# BMSBoard.net
KiCad netlist of a schematic drawn in EAGLE
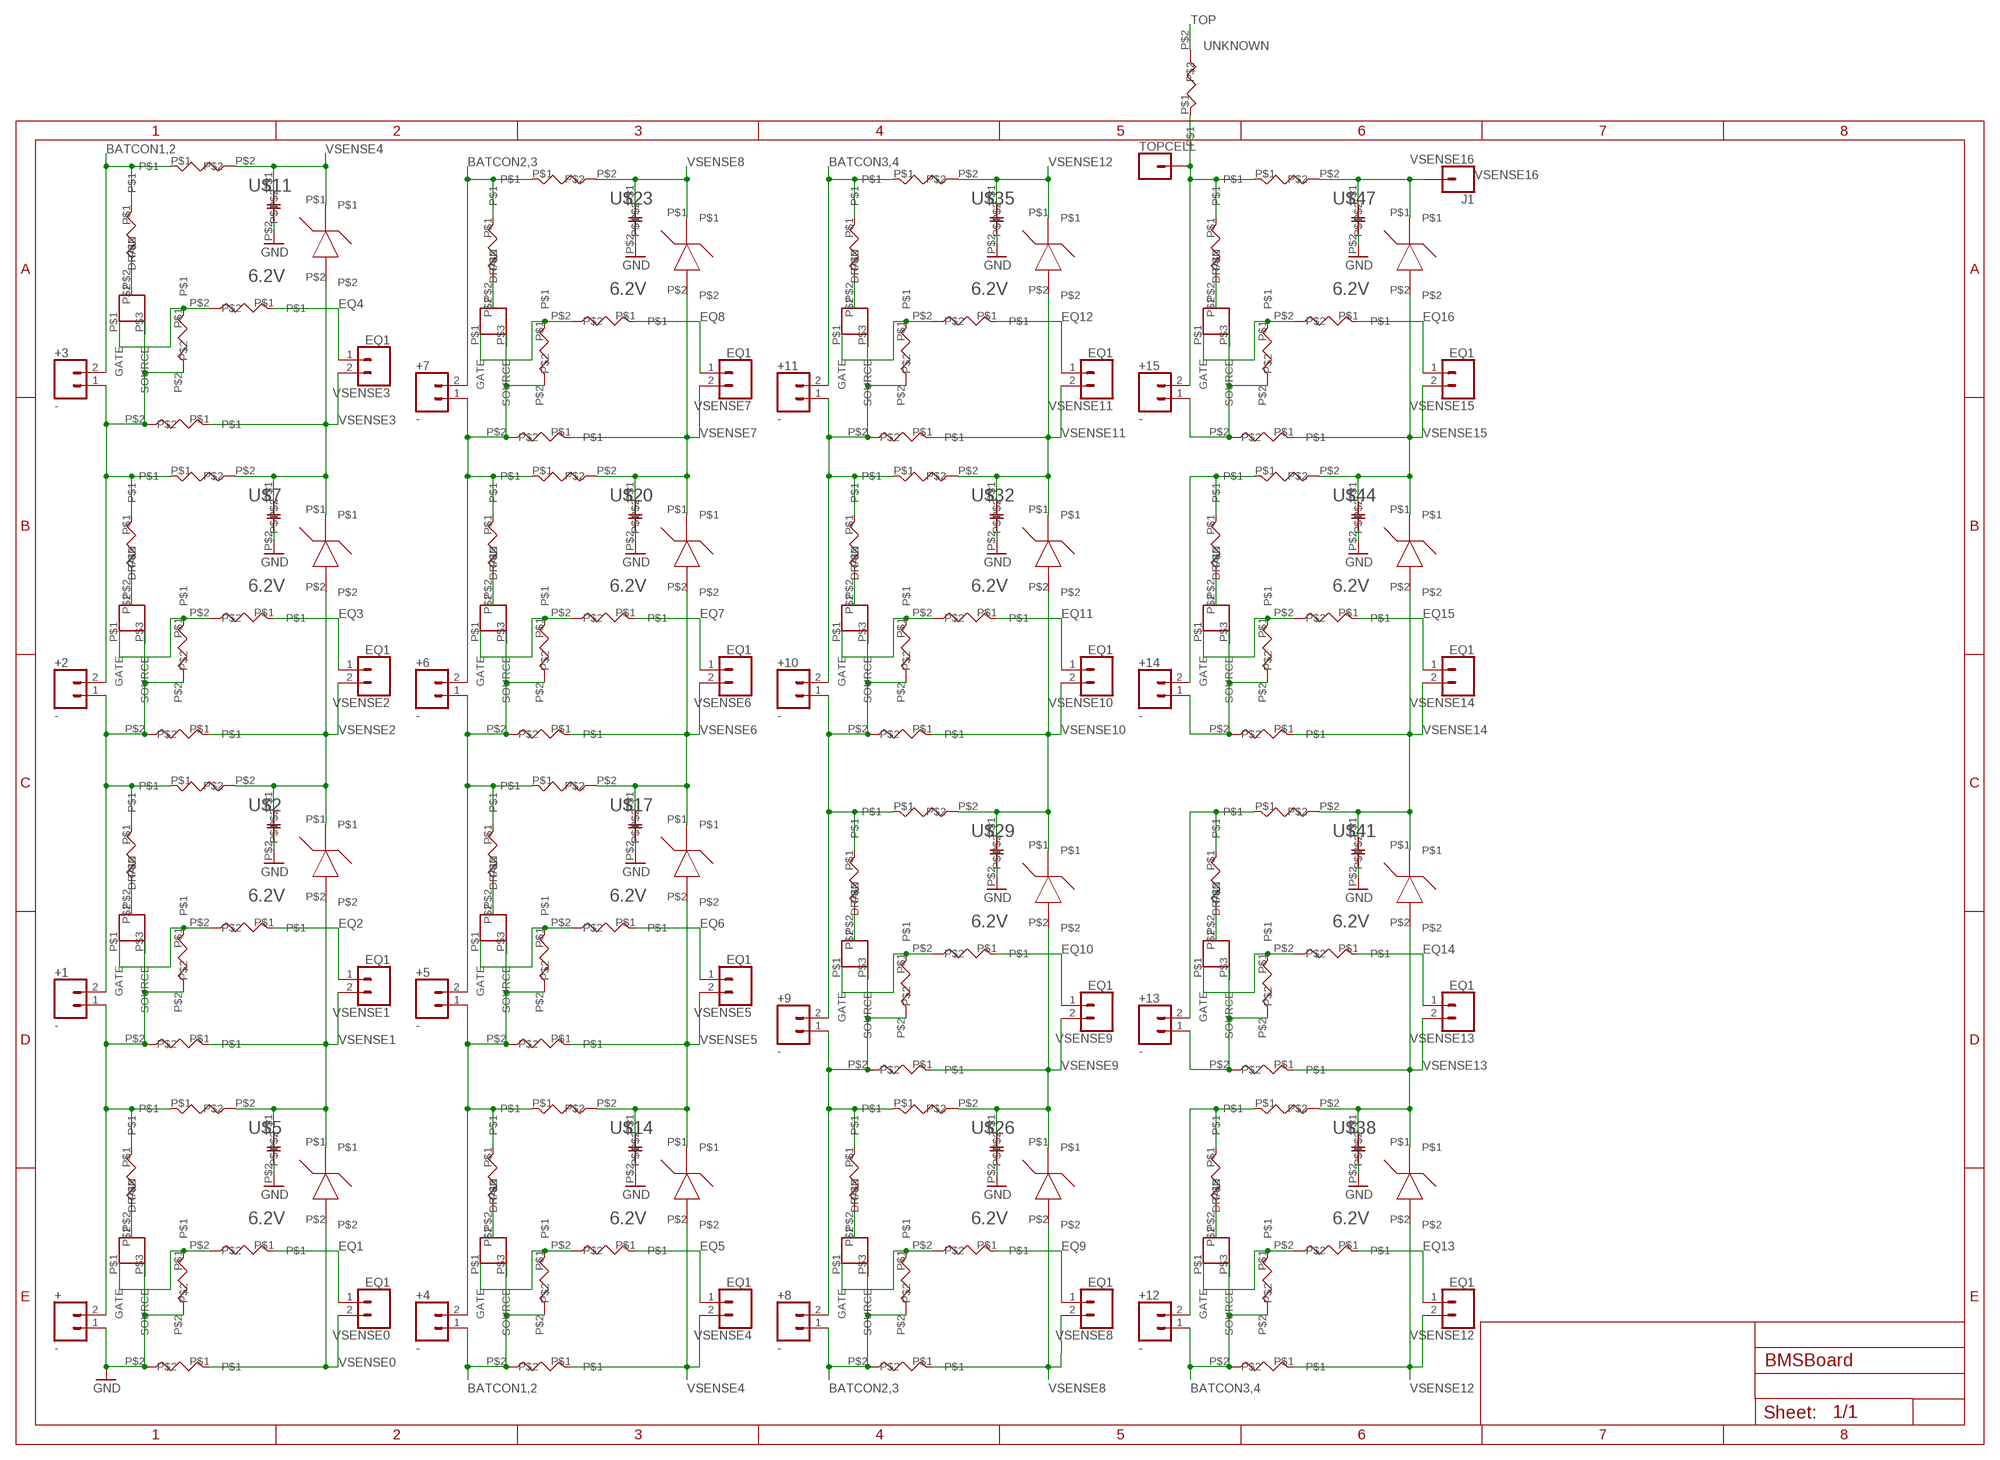
[diagram p0: schematic, sheet 1, part 1 of 2]
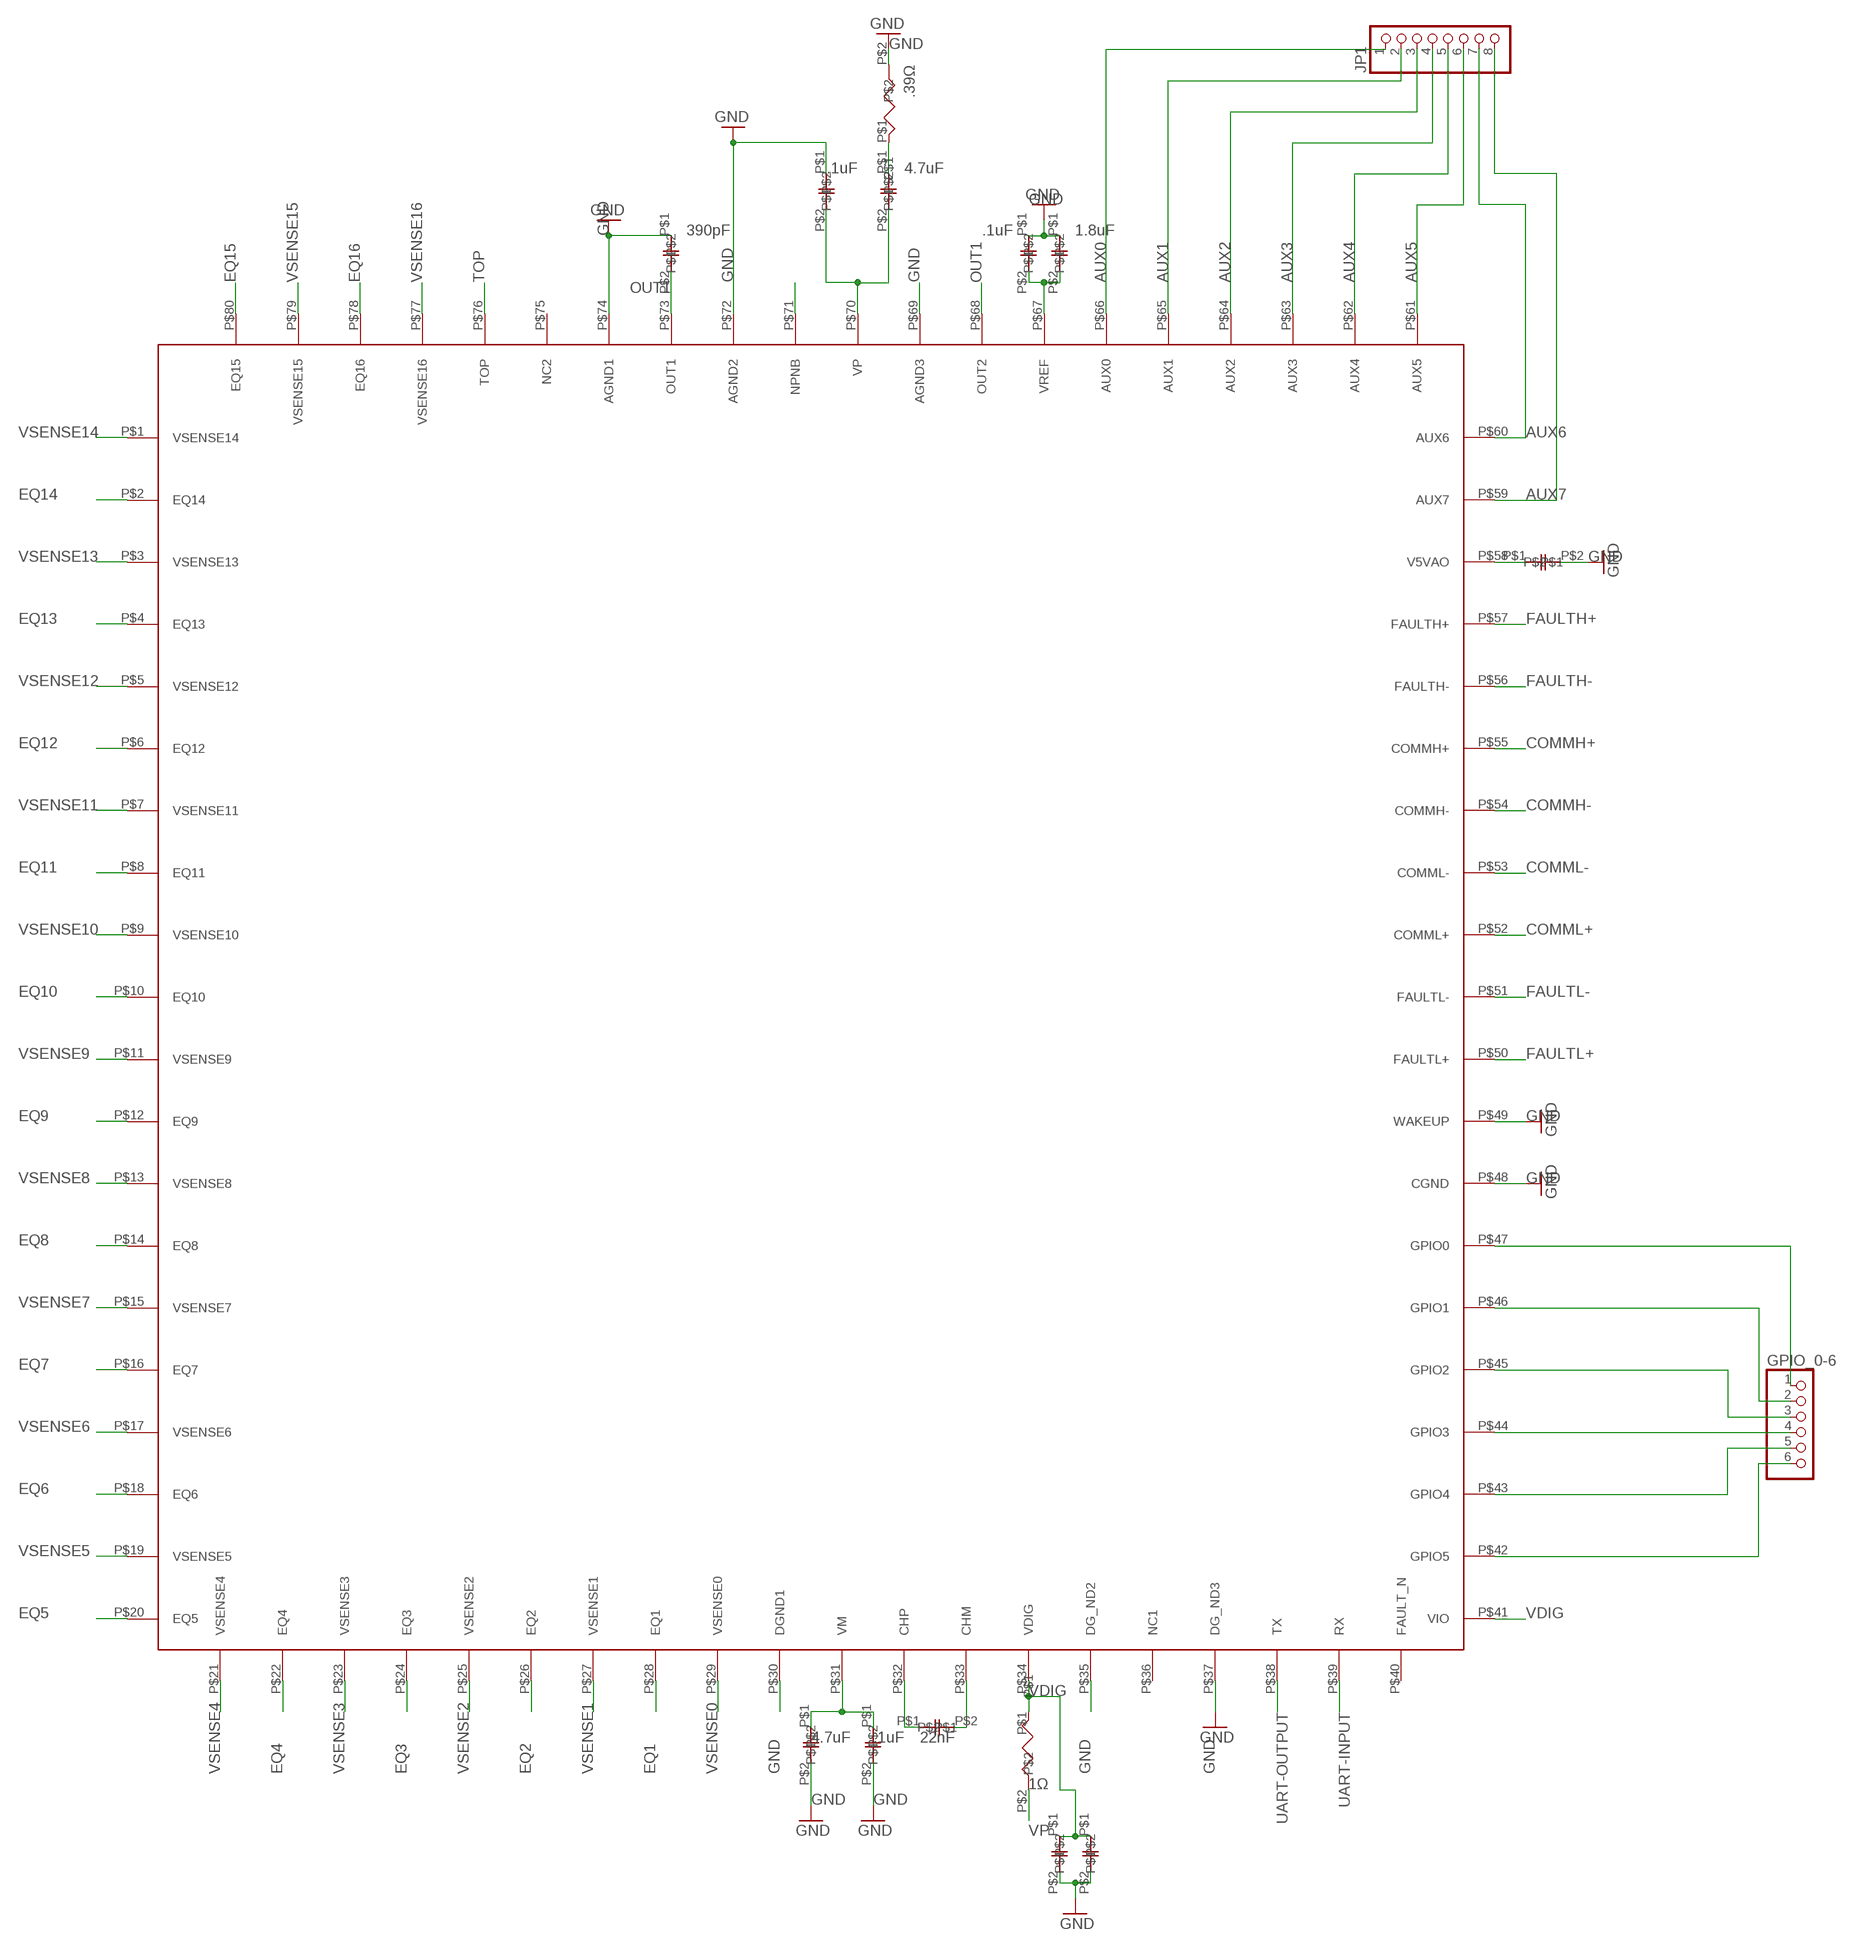
[diagram p1: schematic, sheet 1, part 2 of 2]

(export (version "E")
  (design (tool "Eeschema 10.0.6"))
  (components
    (comp (ref "+")
      (value "-")
      (footprint "eagle-import:1X02")
      (libsource (lib "eagle-import") (part "CONN_02"))
    )
    (comp (ref "+1")
      (value "-")
      (footprint "eagle-import:1X02")
      (libsource (lib "eagle-import") (part "CONN_02"))
    )
    (comp (ref "+2")
      (value "-")
      (footprint "eagle-import:1X02")
      (libsource (lib "eagle-import") (part "CONN_02"))
    )
    (comp (ref "+3")
      (value "-")
      (footprint "eagle-import:1X02")
      (libsource (lib "eagle-import") (part "CONN_02"))
    )
    (comp (ref "+4")
      (value "-")
      (footprint "eagle-import:1X02")
      (libsource (lib "eagle-import") (part "CONN_02"))
    )
    (comp (ref "+5")
      (value "-")
      (footprint "eagle-import:1X02")
      (libsource (lib "eagle-import") (part "CONN_02"))
    )
    (comp (ref "+6")
      (value "-")
      (footprint "eagle-import:1X02")
      (libsource (lib "eagle-import") (part "CONN_02"))
    )
    (comp (ref "+7")
      (value "-")
      (footprint "eagle-import:1X02")
      (libsource (lib "eagle-import") (part "CONN_02"))
    )
    (comp (ref "+8")
      (value "-")
      (footprint "eagle-import:1X02")
      (libsource (lib "eagle-import") (part "CONN_02"))
    )
    (comp (ref "+9")
      (value "-")
      (footprint "eagle-import:1X02")
      (libsource (lib "eagle-import") (part "CONN_02"))
    )
    (comp (ref "+10")
      (value "-")
      (footprint "eagle-import:1X02")
      (libsource (lib "eagle-import") (part "CONN_02"))
    )
    (comp (ref "+11")
      (value "-")
      (footprint "eagle-import:1X02")
      (libsource (lib "eagle-import") (part "CONN_02"))
    )
    (comp (ref "+12")
      (value "-")
      (footprint "eagle-import:1X02")
      (libsource (lib "eagle-import") (part "CONN_02"))
    )
    (comp (ref "+13")
      (value "-")
      (footprint "eagle-import:1X02")
      (libsource (lib "eagle-import") (part "CONN_02"))
    )
    (comp (ref "+14")
      (value "-")
      (footprint "eagle-import:1X02")
      (libsource (lib "eagle-import") (part "CONN_02"))
    )
    (comp (ref "+15")
      (value "-")
      (footprint "eagle-import:1X02")
      (libsource (lib "eagle-import") (part "CONN_02"))
    )
    (comp (ref "1UF")
      (value "1uF")
      (footprint "eagle-import:CL21B105KBFNNNG")
      (libsource (lib "eagle-import") (part "CL21B105KBFNNNG"))
    )
    (comp (ref "1UF1")
      (value "1uF")
      (footprint "eagle-import:CL21B105KBFNNNG")
      (libsource (lib "eagle-import") (part "CL21B105KBFNNNG"))
    )
    (comp (ref "1UF2")
      (value "1uF")
      (footprint "eagle-import:CL21B105KBFNNNG")
      (libsource (lib "eagle-import") (part "CL21B105KBFNNNG"))
    )
    (comp (ref "1UF3")
      (value "1uF")
      (footprint "eagle-import:CL21B105KBFNNNG")
      (libsource (lib "eagle-import") (part "CL21B105KBFNNNG"))
    )
    (comp (ref "1UF4")
      (value "1uF")
      (footprint "eagle-import:CL21B105KBFNNNG")
      (libsource (lib "eagle-import") (part "CL21B105KBFNNNG"))
    )
    (comp (ref "1UF5")
      (value "1uF")
      (footprint "eagle-import:CL21B105KBFNNNG")
      (libsource (lib "eagle-import") (part "CL21B105KBFNNNG"))
    )
    (comp (ref "1UF6")
      (value "1uF")
      (footprint "eagle-import:CL21B105KBFNNNG")
      (libsource (lib "eagle-import") (part "CL21B105KBFNNNG"))
    )
    (comp (ref "1UF7")
      (value "1uF")
      (footprint "eagle-import:CL21B105KBFNNNG")
      (libsource (lib "eagle-import") (part "CL21B105KBFNNNG"))
    )
    (comp (ref "1UF8")
      (value "1uF")
      (footprint "eagle-import:CL21B105KBFNNNG")
      (libsource (lib "eagle-import") (part "CL21B105KBFNNNG"))
    )
    (comp (ref "1UF9")
      (value "1uF")
      (footprint "eagle-import:CL21B105KBFNNNG")
      (libsource (lib "eagle-import") (part "CL21B105KBFNNNG"))
    )
    (comp (ref "1UF10")
      (value "1uF")
      (footprint "eagle-import:CL21B105KBFNNNG")
      (libsource (lib "eagle-import") (part "CL21B105KBFNNNG"))
    )
    (comp (ref "1UF11")
      (value "1uF")
      (footprint "eagle-import:CL21B105KBFNNNG")
      (libsource (lib "eagle-import") (part "CL21B105KBFNNNG"))
    )
    (comp (ref "1UF12")
      (value "1uF")
      (footprint "eagle-import:CL21B105KBFNNNG")
      (libsource (lib "eagle-import") (part "CL21B105KBFNNNG"))
    )
    (comp (ref "1UF13")
      (value "1uF")
      (footprint "eagle-import:CL21B105KBFNNNG")
      (libsource (lib "eagle-import") (part "CL21B105KBFNNNG"))
    )
    (comp (ref "1UF14")
      (value "1uF")
      (footprint "eagle-import:CL21B105KBFNNNG")
      (libsource (lib "eagle-import") (part "CL21B105KBFNNNG"))
    )
    (comp (ref "1UF15")
      (value "1uF")
      (footprint "eagle-import:CL21B105KBFNNNG")
      (libsource (lib "eagle-import") (part "CL21B105KBFNNNG"))
    )
    (comp (ref "2KΩ")
      (value "2kΩ")
      (footprint "eagle-import:PWR3014W1000JE")
      (libsource (lib "eagle-import") (part "PWR3014W1000JE"))
    )
    (comp (ref "2KΩ1")
      (value "2kΩ")
      (footprint "eagle-import:PWR3014W1000JE")
      (libsource (lib "eagle-import") (part "PWR3014W1000JE"))
    )
    (comp (ref "2KΩ2")
      (value "2kΩ")
      (footprint "eagle-import:PWR3014W1000JE")
      (libsource (lib "eagle-import") (part "PWR3014W1000JE"))
    )
    (comp (ref "2KΩ3")
      (value "2kΩ")
      (footprint "eagle-import:PWR3014W1000JE")
      (libsource (lib "eagle-import") (part "PWR3014W1000JE"))
    )
    (comp (ref "2KΩ4")
      (value "2kΩ")
      (footprint "eagle-import:PWR3014W1000JE")
      (libsource (lib "eagle-import") (part "PWR3014W1000JE"))
    )
    (comp (ref "2KΩ5")
      (value "2kΩ")
      (footprint "eagle-import:PWR3014W1000JE")
      (libsource (lib "eagle-import") (part "PWR3014W1000JE"))
    )
    (comp (ref "2KΩ6")
      (value "2kΩ")
      (footprint "eagle-import:PWR3014W1000JE")
      (libsource (lib "eagle-import") (part "PWR3014W1000JE"))
    )
    (comp (ref "2KΩ7")
      (value "2kΩ")
      (footprint "eagle-import:PWR3014W1000JE")
      (libsource (lib "eagle-import") (part "PWR3014W1000JE"))
    )
    (comp (ref "2KΩ8")
      (value "2kΩ")
      (footprint "eagle-import:PWR3014W1000JE")
      (libsource (lib "eagle-import") (part "PWR3014W1000JE"))
    )
    (comp (ref "2KΩ9")
      (value "2kΩ")
      (footprint "eagle-import:PWR3014W1000JE")
      (libsource (lib "eagle-import") (part "PWR3014W1000JE"))
    )
    (comp (ref "2KΩ10")
      (value "2kΩ")
      (footprint "eagle-import:PWR3014W1000JE")
      (libsource (lib "eagle-import") (part "PWR3014W1000JE"))
    )
    (comp (ref "2KΩ11")
      (value "2kΩ")
      (footprint "eagle-import:PWR3014W1000JE")
      (libsource (lib "eagle-import") (part "PWR3014W1000JE"))
    )
    (comp (ref "2KΩ12")
      (value "2kΩ")
      (footprint "eagle-import:PWR3014W1000JE")
      (libsource (lib "eagle-import") (part "PWR3014W1000JE"))
    )
    (comp (ref "2KΩ13")
      (value "2kΩ")
      (footprint "eagle-import:PWR3014W1000JE")
      (libsource (lib "eagle-import") (part "PWR3014W1000JE"))
    )
    (comp (ref "2KΩ14")
      (value "2kΩ")
      (footprint "eagle-import:PWR3014W1000JE")
      (libsource (lib "eagle-import") (part "PWR3014W1000JE"))
    )
    (comp (ref "2KΩ15")
      (value "2kΩ")
      (footprint "eagle-import:PWR3014W1000JE")
      (libsource (lib "eagle-import") (part "PWR3014W1000JE"))
    )
    (comp (ref "75Ω")
      (value "75Ω")
      (footprint "eagle-import:PWR3014W1000JE")
      (libsource (lib "eagle-import") (part "PWR3014W1000JE"))
    )
    (comp (ref "75Ω1")
      (value "75Ω")
      (footprint "eagle-import:PWR3014W1000JE")
      (libsource (lib "eagle-import") (part "PWR3014W1000JE"))
    )
    (comp (ref "75Ω2")
      (value "75Ω")
      (footprint "eagle-import:PWR3014W1000JE")
      (libsource (lib "eagle-import") (part "PWR3014W1000JE"))
    )
    (comp (ref "75Ω3")
      (value "75Ω")
      (footprint "eagle-import:PWR3014W1000JE")
      (libsource (lib "eagle-import") (part "PWR3014W1000JE"))
    )
    (comp (ref "75Ω4")
      (value "75Ω")
      (footprint "eagle-import:PWR3014W1000JE")
      (libsource (lib "eagle-import") (part "PWR3014W1000JE"))
    )
    (comp (ref "75Ω5")
      (value "75Ω")
      (footprint "eagle-import:PWR3014W1000JE")
      (libsource (lib "eagle-import") (part "PWR3014W1000JE"))
    )
    (comp (ref "75Ω6")
      (value "75Ω")
      (footprint "eagle-import:PWR3014W1000JE")
      (libsource (lib "eagle-import") (part "PWR3014W1000JE"))
    )
    (comp (ref "75Ω7")
      (value "75Ω")
      (footprint "eagle-import:PWR3014W1000JE")
      (libsource (lib "eagle-import") (part "PWR3014W1000JE"))
    )
    (comp (ref "75Ω8")
      (value "75Ω")
      (footprint "eagle-import:PWR3014W1000JE")
      (libsource (lib "eagle-import") (part "PWR3014W1000JE"))
    )
    (comp (ref "75Ω9")
      (value "75Ω")
      (footprint "eagle-import:PWR3014W1000JE")
      (libsource (lib "eagle-import") (part "PWR3014W1000JE"))
    )
    (comp (ref "75Ω10")
      (value "75Ω")
      (footprint "eagle-import:PWR3014W1000JE")
      (libsource (lib "eagle-import") (part "PWR3014W1000JE"))
    )
    (comp (ref "75Ω11")
      (value "75Ω")
      (footprint "eagle-import:PWR3014W1000JE")
      (libsource (lib "eagle-import") (part "PWR3014W1000JE"))
    )
    (comp (ref "75Ω12")
      (value "75Ω")
      (footprint "eagle-import:PWR3014W1000JE")
      (libsource (lib "eagle-import") (part "PWR3014W1000JE"))
    )
    (comp (ref "75Ω13")
      (value "75Ω")
      (footprint "eagle-import:PWR3014W1000JE")
      (libsource (lib "eagle-import") (part "PWR3014W1000JE"))
    )
    (comp (ref "75Ω14")
      (value "75Ω")
      (footprint "eagle-import:PWR3014W1000JE")
      (libsource (lib "eagle-import") (part "PWR3014W1000JE"))
    )
    (comp (ref "75Ω15")
      (value "75Ω")
      (footprint "eagle-import:PWR3014W1000JE")
      (libsource (lib "eagle-import") (part "PWR3014W1000JE"))
    )
    (comp (ref "100KΩ")
      (value "100kΩ")
      (footprint "eagle-import:PWR3014W1000JE")
      (libsource (lib "eagle-import") (part "PWR3014W1000JE"))
    )
    (comp (ref "100KΩ1")
      (value "100kΩ")
      (footprint "eagle-import:PWR3014W1000JE")
      (libsource (lib "eagle-import") (part "PWR3014W1000JE"))
    )
    (comp (ref "100KΩ2")
      (value "100kΩ")
      (footprint "eagle-import:PWR3014W1000JE")
      (libsource (lib "eagle-import") (part "PWR3014W1000JE"))
    )
    (comp (ref "100KΩ3")
      (value "100kΩ")
      (footprint "eagle-import:PWR3014W1000JE")
      (libsource (lib "eagle-import") (part "PWR3014W1000JE"))
    )
    (comp (ref "100KΩ4")
      (value "100kΩ")
      (footprint "eagle-import:PWR3014W1000JE")
      (libsource (lib "eagle-import") (part "PWR3014W1000JE"))
    )
    (comp (ref "100KΩ5")
      (value "100kΩ")
      (footprint "eagle-import:PWR3014W1000JE")
      (libsource (lib "eagle-import") (part "PWR3014W1000JE"))
    )
    (comp (ref "100KΩ6")
      (value "100kΩ")
      (footprint "eagle-import:PWR3014W1000JE")
      (libsource (lib "eagle-import") (part "PWR3014W1000JE"))
    )
    (comp (ref "100KΩ7")
      (value "100kΩ")
      (footprint "eagle-import:PWR3014W1000JE")
      (libsource (lib "eagle-import") (part "PWR3014W1000JE"))
    )
    (comp (ref "100KΩ8")
      (value "100kΩ")
      (footprint "eagle-import:PWR3014W1000JE")
      (libsource (lib "eagle-import") (part "PWR3014W1000JE"))
    )
    (comp (ref "100KΩ9")
      (value "100kΩ")
      (footprint "eagle-import:PWR3014W1000JE")
      (libsource (lib "eagle-import") (part "PWR3014W1000JE"))
    )
    (comp (ref "100KΩ10")
      (value "100kΩ")
      (footprint "eagle-import:PWR3014W1000JE")
      (libsource (lib "eagle-import") (part "PWR3014W1000JE"))
    )
    (comp (ref "100KΩ11")
      (value "100kΩ")
      (footprint "eagle-import:PWR3014W1000JE")
      (libsource (lib "eagle-import") (part "PWR3014W1000JE"))
    )
    (comp (ref "100KΩ12")
      (value "100kΩ")
      (footprint "eagle-import:PWR3014W1000JE")
      (libsource (lib "eagle-import") (part "PWR3014W1000JE"))
    )
    (comp (ref "100KΩ13")
      (value "100kΩ")
      (footprint "eagle-import:PWR3014W1000JE")
      (libsource (lib "eagle-import") (part "PWR3014W1000JE"))
    )
    (comp (ref "100KΩ14")
      (value "100kΩ")
      (footprint "eagle-import:PWR3014W1000JE")
      (libsource (lib "eagle-import") (part "PWR3014W1000JE"))
    )
    (comp (ref "100KΩ15")
      (value "100kΩ")
      (footprint "eagle-import:PWR3014W1000JE")
      (libsource (lib "eagle-import") (part "PWR3014W1000JE"))
    )
    (comp (ref "100Ω")
      (value "100Ω")
      (footprint "eagle-import:PWR3014W1000JE")
      (libsource (lib "eagle-import") (part "PWR3014W1000JE"))
    )
    (comp (ref "100Ω1")
      (value "100Ω")
      (footprint "eagle-import:PWR3014W1000JE")
      (libsource (lib "eagle-import") (part "PWR3014W1000JE"))
    )
    (comp (ref "100Ω2")
      (value "100Ω")
      (footprint "eagle-import:PWR3014W1000JE")
      (libsource (lib "eagle-import") (part "PWR3014W1000JE"))
    )
    (comp (ref "100Ω3")
      (value "100Ω")
      (footprint "eagle-import:PWR3014W1000JE")
      (libsource (lib "eagle-import") (part "PWR3014W1000JE"))
    )
    (comp (ref "100Ω4")
      (value "100Ω")
      (footprint "eagle-import:PWR3014W1000JE")
      (libsource (lib "eagle-import") (part "PWR3014W1000JE"))
    )
    (comp (ref "100Ω5")
      (value "100Ω")
      (footprint "eagle-import:PWR3014W1000JE")
      (libsource (lib "eagle-import") (part "PWR3014W1000JE"))
    )
    (comp (ref "100Ω6")
      (value "100Ω")
      (footprint "eagle-import:PWR3014W1000JE")
      (libsource (lib "eagle-import") (part "PWR3014W1000JE"))
    )
    (comp (ref "100Ω7")
      (value "100Ω")
      (footprint "eagle-import:PWR3014W1000JE")
      (libsource (lib "eagle-import") (part "PWR3014W1000JE"))
    )
    (comp (ref "100Ω8")
      (value "100Ω")
      (footprint "eagle-import:PWR3014W1000JE")
      (libsource (lib "eagle-import") (part "PWR3014W1000JE"))
    )
    (comp (ref "100Ω9")
      (value "100Ω")
      (footprint "eagle-import:PWR3014W1000JE")
      (libsource (lib "eagle-import") (part "PWR3014W1000JE"))
    )
    (comp (ref "100Ω10")
      (value "100Ω")
      (footprint "eagle-import:PWR3014W1000JE")
      (libsource (lib "eagle-import") (part "PWR3014W1000JE"))
    )
    (comp (ref "100Ω11")
      (value "100Ω")
      (footprint "eagle-import:PWR3014W1000JE")
      (libsource (lib "eagle-import") (part "PWR3014W1000JE"))
    )
    (comp (ref "100Ω12")
      (value "100Ω")
      (footprint "eagle-import:PWR3014W1000JE")
      (libsource (lib "eagle-import") (part "PWR3014W1000JE"))
    )
    (comp (ref "100Ω13")
      (value "100Ω")
      (footprint "eagle-import:PWR3014W1000JE")
      (libsource (lib "eagle-import") (part "PWR3014W1000JE"))
    )
    (comp (ref "100Ω14")
      (value "100Ω")
      (footprint "eagle-import:PWR3014W1000JE")
      (libsource (lib "eagle-import") (part "PWR3014W1000JE"))
    )
    (comp (ref "100Ω15")
      (value "100Ω")
      (footprint "eagle-import:PWR3014W1000JE")
      (libsource (lib "eagle-import") (part "PWR3014W1000JE"))
    )
    (comp (ref "GPIO_0-6")
      (value "PINHD-1X6")
      (footprint "eagle-import:1X06")
      (libsource (lib "eagle-import") (part "PINHD-1X6"))
    )
    (comp (ref "J1")
      (value "VSENSE16")
      (footprint "eagle-import:1X01")
      (libsource (lib "eagle-import") (part "CONN_01"))
    )
    (comp (ref "JP1")
      (value "PINHD-1X8BIG")
      (footprint "eagle-import:1X08-BIG")
      (libsource (lib "eagle-import") (part "PINHD-1X8BIG"))
    )
    (comp (ref "TOPCELL")
      (value "CONN_01")
      (footprint "eagle-import:1X01")
      (libsource (lib "eagle-import") (part "CONN_01"))
    )
    (comp (ref "U$1")
      (value "2V7002KT1G")
      (footprint "eagle-import:2V7002KT1G")
      (libsource (lib "eagle-import") (part "2V7002KT1G"))
    )
    (comp (ref "U$2")
      (value "6.2V")
      (footprint "eagle-import:SOD-123-2")
      (libsource (lib "eagle-import") (part "PDZ6.2BGWX"))
    )
    (comp (ref "U$3")
      (value "100Ω")
      (footprint "eagle-import:PWR3014W1000JE")
      (libsource (lib "eagle-import") (part "PWR3014W1000JE"))
    )
    (comp (ref "U$4")
      (value "2V7002KT1G")
      (footprint "eagle-import:2V7002KT1G")
      (libsource (lib "eagle-import") (part "2V7002KT1G"))
    )
    (comp (ref "U$5")
      (value "6.2V")
      (footprint "eagle-import:SOD-123-2")
      (libsource (lib "eagle-import") (part "PDZ6.2BGWX"))
    )
    (comp (ref "U$6")
      (value "2V7002KT1G")
      (footprint "eagle-import:2V7002KT1G")
      (libsource (lib "eagle-import") (part "2V7002KT1G"))
    )
    (comp (ref "U$7")
      (value "6.2V")
      (footprint "eagle-import:SOD-123-2")
      (libsource (lib "eagle-import") (part "PDZ6.2BGWX"))
    )
    (comp (ref "U$8")
      (value "100Ω")
      (footprint "eagle-import:PWR3014W1000JE")
      (libsource (lib "eagle-import") (part "PWR3014W1000JE"))
    )
    (comp (ref "U$9")
      (value "100Ω")
      (footprint "eagle-import:PWR3014W1000JE")
      (libsource (lib "eagle-import") (part "PWR3014W1000JE"))
    )
    (comp (ref "U$10")
      (value "2V7002KT1G")
      (footprint "eagle-import:2V7002KT1G")
      (libsource (lib "eagle-import") (part "2V7002KT1G"))
    )
    (comp (ref "U$11")
      (value "6.2V")
      (footprint "eagle-import:SOD-123-2")
      (libsource (lib "eagle-import") (part "PDZ6.2BGWX"))
    )
    (comp (ref "U$12")
      (value "100Ω")
      (footprint "eagle-import:PWR3014W1000JE")
      (libsource (lib "eagle-import") (part "PWR3014W1000JE"))
    )
    (comp (ref "U$13")
      (value "2V7002KT1G")
      (footprint "eagle-import:2V7002KT1G")
      (libsource (lib "eagle-import") (part "2V7002KT1G"))
    )
    (comp (ref "U$14")
      (value "6.2V")
      (footprint "eagle-import:SOD-123-2")
      (libsource (lib "eagle-import") (part "PDZ6.2BGWX"))
    )
    (comp (ref "U$15")
      (value "100Ω")
      (footprint "eagle-import:PWR3014W1000JE")
      (libsource (lib "eagle-import") (part "PWR3014W1000JE"))
    )
    (comp (ref "U$16")
      (value "2V7002KT1G")
      (footprint "eagle-import:2V7002KT1G")
      (libsource (lib "eagle-import") (part "2V7002KT1G"))
    )
    (comp (ref "U$17")
      (value "6.2V")
      (footprint "eagle-import:SOD-123-2")
      (libsource (lib "eagle-import") (part "PDZ6.2BGWX"))
    )
    (comp (ref "U$18")
      (value "100Ω")
      (footprint "eagle-import:PWR3014W1000JE")
      (libsource (lib "eagle-import") (part "PWR3014W1000JE"))
    )
    (comp (ref "U$19")
      (value "2V7002KT1G")
      (footprint "eagle-import:2V7002KT1G")
      (libsource (lib "eagle-import") (part "2V7002KT1G"))
    )
    (comp (ref "U$20")
      (value "6.2V")
      (footprint "eagle-import:SOD-123-2")
      (libsource (lib "eagle-import") (part "PDZ6.2BGWX"))
    )
    (comp (ref "U$21")
      (value "100Ω")
      (footprint "eagle-import:PWR3014W1000JE")
      (libsource (lib "eagle-import") (part "PWR3014W1000JE"))
    )
    (comp (ref "U$22")
      (value "2V7002KT1G")
      (footprint "eagle-import:2V7002KT1G")
      (libsource (lib "eagle-import") (part "2V7002KT1G"))
    )
    (comp (ref "U$23")
      (value "6.2V")
      (footprint "eagle-import:SOD-123-2")
      (libsource (lib "eagle-import") (part "PDZ6.2BGWX"))
    )
    (comp (ref "U$24")
      (value "100Ω")
      (footprint "eagle-import:PWR3014W1000JE")
      (libsource (lib "eagle-import") (part "PWR3014W1000JE"))
    )
    (comp (ref "U$25")
      (value "2V7002KT1G")
      (footprint "eagle-import:2V7002KT1G")
      (libsource (lib "eagle-import") (part "2V7002KT1G"))
    )
    (comp (ref "U$26")
      (value "6.2V")
      (footprint "eagle-import:SOD-123-2")
      (libsource (lib "eagle-import") (part "PDZ6.2BGWX"))
    )
    (comp (ref "U$27")
      (value "100Ω")
      (footprint "eagle-import:PWR3014W1000JE")
      (libsource (lib "eagle-import") (part "PWR3014W1000JE"))
    )
    (comp (ref "U$28")
      (value "2V7002KT1G")
      (footprint "eagle-import:2V7002KT1G")
      (libsource (lib "eagle-import") (part "2V7002KT1G"))
    )
    (comp (ref "U$29")
      (value "6.2V")
      (footprint "eagle-import:SOD-123-2")
      (libsource (lib "eagle-import") (part "PDZ6.2BGWX"))
    )
    (comp (ref "U$30")
      (value "100Ω")
      (footprint "eagle-import:PWR3014W1000JE")
      (libsource (lib "eagle-import") (part "PWR3014W1000JE"))
    )
    (comp (ref "U$31")
      (value "2V7002KT1G")
      (footprint "eagle-import:2V7002KT1G")
      (libsource (lib "eagle-import") (part "2V7002KT1G"))
    )
    (comp (ref "U$32")
      (value "6.2V")
      (footprint "eagle-import:SOD-123-2")
      (libsource (lib "eagle-import") (part "PDZ6.2BGWX"))
    )
    (comp (ref "U$33")
      (value "100Ω")
      (footprint "eagle-import:PWR3014W1000JE")
      (libsource (lib "eagle-import") (part "PWR3014W1000JE"))
    )
    (comp (ref "U$34")
      (value "2V7002KT1G")
      (footprint "eagle-import:2V7002KT1G")
      (libsource (lib "eagle-import") (part "2V7002KT1G"))
    )
    (comp (ref "U$35")
      (value "6.2V")
      (footprint "eagle-import:SOD-123-2")
      (libsource (lib "eagle-import") (part "PDZ6.2BGWX"))
    )
    (comp (ref "U$36")
      (value "100Ω")
      (footprint "eagle-import:PWR3014W1000JE")
      (libsource (lib "eagle-import") (part "PWR3014W1000JE"))
    )
    (comp (ref "U$37")
      (value "2V7002KT1G")
      (footprint "eagle-import:2V7002KT1G")
      (libsource (lib "eagle-import") (part "2V7002KT1G"))
    )
    (comp (ref "U$38")
      (value "6.2V")
      (footprint "eagle-import:SOD-123-2")
      (libsource (lib "eagle-import") (part "PDZ6.2BGWX"))
    )
    (comp (ref "U$39")
      (value "100Ω")
      (footprint "eagle-import:PWR3014W1000JE")
      (libsource (lib "eagle-import") (part "PWR3014W1000JE"))
    )
    (comp (ref "U$40")
      (value "2V7002KT1G")
      (footprint "eagle-import:2V7002KT1G")
      (libsource (lib "eagle-import") (part "2V7002KT1G"))
    )
    (comp (ref "U$41")
      (value "6.2V")
      (footprint "eagle-import:SOD-123-2")
      (libsource (lib "eagle-import") (part "PDZ6.2BGWX"))
    )
    (comp (ref "U$42")
      (value "100Ω")
      (footprint "eagle-import:PWR3014W1000JE")
      (libsource (lib "eagle-import") (part "PWR3014W1000JE"))
    )
    (comp (ref "U$43")
      (value "2V7002KT1G")
      (footprint "eagle-import:2V7002KT1G")
      (libsource (lib "eagle-import") (part "2V7002KT1G"))
    )
    (comp (ref "U$44")
      (value "6.2V")
      (footprint "eagle-import:SOD-123-2")
      (libsource (lib "eagle-import") (part "PDZ6.2BGWX"))
    )
    (comp (ref "U$45")
      (value "100Ω")
      (footprint "eagle-import:PWR3014W1000JE")
      (libsource (lib "eagle-import") (part "PWR3014W1000JE"))
    )
    (comp (ref "U$46")
      (value "2V7002KT1G")
      (footprint "eagle-import:2V7002KT1G")
      (libsource (lib "eagle-import") (part "2V7002KT1G"))
    )
    (comp (ref "U$47")
      (value "6.2V")
      (footprint "eagle-import:SOD-123-2")
      (libsource (lib "eagle-import") (part "PDZ6.2BGWX"))
    )
    (comp (ref "U$48")
      (value "100Ω")
      (footprint "eagle-import:PWR3014W1000JE")
      (libsource (lib "eagle-import") (part "PWR3014W1000JE"))
    )
    (comp (ref "U$49")
      (value "BQ76PL455A-Q1")
      (footprint "eagle-import:BQ76PL455A-Q1")
      (libsource (lib "eagle-import") (part "BQ76PL455A-Q1"))
    )
    (comp (ref "U$50")
      (value "22nF")
      (footprint "eagle-import:CL21B105KBFNNNG")
      (fields (field (name "CHP-CHM") "22nF"))
      (libsource (lib "eagle-import") (part "CL21B105KBFNNNG"))
    )
    (comp (ref "U$51")
      (value "CL21B105KBFNNNG")
      (footprint "eagle-import:CL21B105KBFNNNG")
      (fields (field (name "VMCAP1") "4.7uF"))
      (libsource (lib "eagle-import") (part "CL21B105KBFNNNG"))
    )
    (comp (ref "U$52")
      (value "CL21B105KBFNNNG")
      (footprint "eagle-import:CL21B105KBFNNNG")
      (fields (field (name "VMCAP2") ".1uF"))
      (libsource (lib "eagle-import") (part "CL21B105KBFNNNG"))
    )
    (comp (ref "U$53")
      (value "1Ω")
      (footprint "eagle-import:PWR3014W1000JE")
      (fields (field (name "VDIG-VP-RESIST") "1Ω"))
      (libsource (lib "eagle-import") (part "PWR3014W1000JE"))
    )
    (comp (ref "U$54")
      (value "CL21B105KBFNNNG")
      (footprint "eagle-import:CL21B105KBFNNNG")
      (libsource (lib "eagle-import") (part "CL21B105KBFNNNG"))
    )
    (comp (ref "U$55")
      (value "CL21B105KBFNNNG")
      (footprint "eagle-import:CL21B105KBFNNNG")
      (libsource (lib "eagle-import") (part "CL21B105KBFNNNG"))
    )
    (comp (ref "U$56")
      (value "CL21B105KBFNNNG")
      (footprint "eagle-import:CL21B105KBFNNNG")
      (libsource (lib "eagle-import") (part "CL21B105KBFNNNG"))
    )
    (comp (ref "U$57")
      (value "CL21B105KBFNNNG")
      (footprint "eagle-import:CL21B105KBFNNNG")
      (fields (field (name "VREFCAP1") ".1uF"))
      (libsource (lib "eagle-import") (part "CL21B105KBFNNNG"))
    )
    (comp (ref "U$58")
      (value "CL21B105KBFNNNG")
      (footprint "eagle-import:CL21B105KBFNNNG")
      (fields (field (name "VREFCAP2") "1.8uF"))
      (libsource (lib "eagle-import") (part "CL21B105KBFNNNG"))
    )
    (comp (ref "U$59")
      (value "CL21B105KBFNNNG")
      (footprint "eagle-import:CL21B105KBFNNNG")
      (fields (field (name "OUT-CAP") "390pF"))
      (libsource (lib "eagle-import") (part "CL21B105KBFNNNG"))
    )
    (comp (ref "U$60")
      (value "CL21B105KBFNNNG")
      (footprint "eagle-import:CL21B105KBFNNNG")
      (fields (field (name "VP-AGND-CAP") ".1uF"))
      (libsource (lib "eagle-import") (part "CL21B105KBFNNNG"))
    )
    (comp (ref "U$61")
      (value "CL21B105KBFNNNG")
      (footprint "eagle-import:CL21B105KBFNNNG")
      (fields (field (name "VP-GND-CAP") "4.7uF"))
      (libsource (lib "eagle-import") (part "CL21B105KBFNNNG"))
    )
    (comp (ref "U$62")
      (value "PWR3014W1000JE")
      (footprint "eagle-import:PWR3014W1000JE")
      (fields (field (name "VP-RESIST") ".39Ω"))
      (libsource (lib "eagle-import") (part "PWR3014W1000JE"))
    )
    (comp (ref "U$63")
      (value "PWR3014W1000JE")
      (footprint "eagle-import:PWR3014W1000JE")
      (fields (field (name "TOP-RESIST") "UNKNOWN"))
      (libsource (lib "eagle-import") (part "PWR3014W1000JE"))
    )
    (comp (ref "VSENSE0")
      (value "EQ1")
      (footprint "eagle-import:1X02")
      (libsource (lib "eagle-import") (part "CONN_02"))
    )
    (comp (ref "VSENSE1")
      (value "EQ1")
      (footprint "eagle-import:1X02")
      (libsource (lib "eagle-import") (part "CONN_02"))
    )
    (comp (ref "VSENSE2")
      (value "EQ1")
      (footprint "eagle-import:1X02")
      (libsource (lib "eagle-import") (part "CONN_02"))
    )
    (comp (ref "VSENSE3")
      (value "EQ1")
      (footprint "eagle-import:1X02")
      (libsource (lib "eagle-import") (part "CONN_02"))
    )
    (comp (ref "VSENSE4")
      (value "EQ1")
      (footprint "eagle-import:1X02")
      (libsource (lib "eagle-import") (part "CONN_02"))
    )
    (comp (ref "VSENSE5")
      (value "EQ1")
      (footprint "eagle-import:1X02")
      (libsource (lib "eagle-import") (part "CONN_02"))
    )
    (comp (ref "VSENSE6")
      (value "EQ1")
      (footprint "eagle-import:1X02")
      (libsource (lib "eagle-import") (part "CONN_02"))
    )
    (comp (ref "VSENSE7")
      (value "EQ1")
      (footprint "eagle-import:1X02")
      (libsource (lib "eagle-import") (part "CONN_02"))
    )
    (comp (ref "VSENSE8")
      (value "EQ1")
      (footprint "eagle-import:1X02")
      (libsource (lib "eagle-import") (part "CONN_02"))
    )
    (comp (ref "VSENSE9")
      (value "EQ1")
      (footprint "eagle-import:1X02")
      (libsource (lib "eagle-import") (part "CONN_02"))
    )
    (comp (ref "VSENSE10")
      (value "EQ1")
      (footprint "eagle-import:1X02")
      (libsource (lib "eagle-import") (part "CONN_02"))
    )
    (comp (ref "VSENSE11")
      (value "EQ1")
      (footprint "eagle-import:1X02")
      (libsource (lib "eagle-import") (part "CONN_02"))
    )
    (comp (ref "VSENSE12")
      (value "EQ1")
      (footprint "eagle-import:1X02")
      (libsource (lib "eagle-import") (part "CONN_02"))
    )
    (comp (ref "VSENSE13")
      (value "EQ1")
      (footprint "eagle-import:1X02")
      (libsource (lib "eagle-import") (part "CONN_02"))
    )
    (comp (ref "VSENSE14")
      (value "EQ1")
      (footprint "eagle-import:1X02")
      (libsource (lib "eagle-import") (part "CONN_02"))
    )
    (comp (ref "VSENSE15")
      (value "EQ1")
      (footprint "eagle-import:1X02")
      (fields (field (name "SPICEPREFIX") "I"))
      (libsource (lib "eagle-import") (part "CONN_02"))
    )
  )
  (nets
    (net (code "1") (name "/AUX0") (class "Default")
      (node (ref "JP1") (pin "1") (pinfunction "1_1") (pintype "passive"))
      (node (ref "U$49") (pin "P$66") (pinfunction "AUX0_P$66") (pintype "bidirectional"))
    )
    (net (code "2") (name "/AUX1") (class "Default")
      (node (ref "JP1") (pin "2") (pinfunction "2_2") (pintype "passive"))
      (node (ref "U$49") (pin "P$65") (pinfunction "AUX1_P$65") (pintype "bidirectional"))
    )
    (net (code "3") (name "/AUX2") (class "Default")
      (node (ref "JP1") (pin "3") (pinfunction "3_3") (pintype "passive"))
      (node (ref "U$49") (pin "P$64") (pinfunction "AUX2_P$64") (pintype "bidirectional"))
    )
    (net (code "4") (name "/AUX3") (class "Default")
      (node (ref "JP1") (pin "4") (pinfunction "4_4") (pintype "passive"))
      (node (ref "U$49") (pin "P$63") (pinfunction "AUX3_P$63") (pintype "bidirectional"))
    )
    (net (code "5") (name "/AUX4") (class "Default")
      (node (ref "JP1") (pin "5") (pinfunction "5_5") (pintype "passive"))
      (node (ref "U$49") (pin "P$62") (pinfunction "AUX4_P$62") (pintype "bidirectional"))
    )
    (net (code "6") (name "/AUX5") (class "Default")
      (node (ref "JP1") (pin "6") (pinfunction "6_6") (pintype "passive"))
      (node (ref "U$49") (pin "P$61") (pinfunction "AUX5_P$61") (pintype "bidirectional"))
    )
    (net (code "7") (name "/AUX6") (class "Default")
      (node (ref "JP1") (pin "7") (pinfunction "7_7") (pintype "passive"))
      (node (ref "U$49") (pin "P$60") (pinfunction "AUX6_P$60") (pintype "bidirectional"))
    )
    (net (code "8") (name "/AUX7") (class "Default")
      (node (ref "JP1") (pin "8") (pinfunction "8_8") (pintype "passive"))
      (node (ref "U$49") (pin "P$59") (pinfunction "AUX7_P$59") (pintype "bidirectional"))
    )
    (net (code "9") (name "/BATCON1,2") (class "Default")
      (node (ref "+3") (pin "2") (pinfunction "2_2") (pintype "passive"))
      (node (ref "+4") (pin "1") (pinfunction "1_1") (pintype "passive"))
      (node (ref "100KΩ4") (pin "P$2") (pinfunction "P$2_P$2") (pintype "bidirectional"))
      (node (ref "100Ω4") (pin "P$2") (pinfunction "P$2_P$2") (pintype "bidirectional"))
      (node (ref "75Ω3") (pin "P$1") (pinfunction "P$1_P$1") (pintype "bidirectional"))
      (node (ref "U$12") (pin "P$1") (pinfunction "P$1_P$1") (pintype "bidirectional"))
      (node (ref "U$13") (pin "P$3") (pinfunction "SOURCE_P$3") (pintype "bidirectional"))
    )
    (net (code "10") (name "/BATCON2,3") (class "Default")
      (node (ref "+7") (pin "2") (pinfunction "2_2") (pintype "passive"))
      (node (ref "+8") (pin "1") (pinfunction "1_1") (pintype "passive"))
      (node (ref "100KΩ8") (pin "P$2") (pinfunction "P$2_P$2") (pintype "bidirectional"))
      (node (ref "100Ω8") (pin "P$2") (pinfunction "P$2_P$2") (pintype "bidirectional"))
      (node (ref "75Ω7") (pin "P$1") (pinfunction "P$1_P$1") (pintype "bidirectional"))
      (node (ref "U$24") (pin "P$1") (pinfunction "P$1_P$1") (pintype "bidirectional"))
      (node (ref "U$25") (pin "P$3") (pinfunction "SOURCE_P$3") (pintype "bidirectional"))
    )
    (net (code "11") (name "/BATCON3,4") (class "Default")
      (node (ref "+11") (pin "2") (pinfunction "2_2") (pintype "passive"))
      (node (ref "+12") (pin "1") (pinfunction "1_1") (pintype "passive"))
      (node (ref "100KΩ12") (pin "P$2") (pinfunction "P$2_P$2") (pintype "bidirectional"))
      (node (ref "100Ω12") (pin "P$2") (pinfunction "P$2_P$2") (pintype "bidirectional"))
      (node (ref "75Ω11") (pin "P$1") (pinfunction "P$1_P$1") (pintype "bidirectional"))
      (node (ref "U$36") (pin "P$1") (pinfunction "P$1_P$1") (pintype "bidirectional"))
      (node (ref "U$37") (pin "P$3") (pinfunction "SOURCE_P$3") (pintype "bidirectional"))
    )
    (net (code "12") (name "/COMMH+") (class "Default")
      (node (ref "U$49") (pin "P$55") (pinfunction "COMMH+_P$55") (pintype "bidirectional"))
    )
    (net (code "13") (name "/COMMH-") (class "Default")
      (node (ref "U$49") (pin "P$54") (pinfunction "COMMH-_P$54") (pintype "bidirectional"))
    )
    (net (code "14") (name "/COMML+") (class "Default")
      (node (ref "U$49") (pin "P$52") (pinfunction "COMML+_P$52") (pintype "bidirectional"))
    )
    (net (code "15") (name "/COMML-") (class "Default")
      (node (ref "U$49") (pin "P$53") (pinfunction "COMML-_P$53") (pintype "bidirectional"))
    )
    (net (code "16") (name "/EQ1") (class "Default")
      (node (ref "2KΩ") (pin "P$1") (pinfunction "P$1_P$1") (pintype "bidirectional"))
      (node (ref "U$49") (pin "P$28") (pinfunction "EQ1_P$28") (pintype "bidirectional"))
      (node (ref "VSENSE0") (pin "1") (pinfunction "1_1") (pintype "passive"))
    )
    (net (code "17") (name "/EQ2") (class "Default")
      (node (ref "2KΩ1") (pin "P$1") (pinfunction "P$1_P$1") (pintype "bidirectional"))
      (node (ref "U$49") (pin "P$26") (pinfunction "EQ2_P$26") (pintype "bidirectional"))
      (node (ref "VSENSE1") (pin "1") (pinfunction "1_1") (pintype "passive"))
    )
    (net (code "18") (name "/EQ3") (class "Default")
      (node (ref "2KΩ2") (pin "P$1") (pinfunction "P$1_P$1") (pintype "bidirectional"))
      (node (ref "U$49") (pin "P$24") (pinfunction "EQ3_P$24") (pintype "bidirectional"))
      (node (ref "VSENSE2") (pin "1") (pinfunction "1_1") (pintype "passive"))
    )
    (net (code "19") (name "/EQ4") (class "Default")
      (node (ref "2KΩ3") (pin "P$1") (pinfunction "P$1_P$1") (pintype "bidirectional"))
      (node (ref "U$49") (pin "P$22") (pinfunction "EQ4_P$22") (pintype "bidirectional"))
      (node (ref "VSENSE3") (pin "1") (pinfunction "1_1") (pintype "passive"))
    )
    (net (code "20") (name "/EQ5") (class "Default")
      (node (ref "2KΩ4") (pin "P$1") (pinfunction "P$1_P$1") (pintype "bidirectional"))
      (node (ref "U$49") (pin "P$20") (pinfunction "EQ5_P$20") (pintype "bidirectional"))
      (node (ref "VSENSE4") (pin "1") (pinfunction "1_1") (pintype "passive"))
    )
    (net (code "21") (name "/EQ6") (class "Default")
      (node (ref "2KΩ5") (pin "P$1") (pinfunction "P$1_P$1") (pintype "bidirectional"))
      (node (ref "U$49") (pin "P$18") (pinfunction "EQ6_P$18") (pintype "bidirectional"))
      (node (ref "VSENSE5") (pin "1") (pinfunction "1_1") (pintype "passive"))
    )
    (net (code "22") (name "/EQ7") (class "Default")
      (node (ref "2KΩ6") (pin "P$1") (pinfunction "P$1_P$1") (pintype "bidirectional"))
      (node (ref "U$49") (pin "P$16") (pinfunction "EQ7_P$16") (pintype "bidirectional"))
      (node (ref "VSENSE6") (pin "1") (pinfunction "1_1") (pintype "passive"))
    )
    (net (code "23") (name "/EQ8") (class "Default")
      (node (ref "2KΩ7") (pin "P$1") (pinfunction "P$1_P$1") (pintype "bidirectional"))
      (node (ref "U$49") (pin "P$14") (pinfunction "EQ8_P$14") (pintype "bidirectional"))
      (node (ref "VSENSE7") (pin "1") (pinfunction "1_1") (pintype "passive"))
    )
    (net (code "24") (name "/EQ9") (class "Default")
      (node (ref "2KΩ8") (pin "P$1") (pinfunction "P$1_P$1") (pintype "bidirectional"))
      (node (ref "U$49") (pin "P$12") (pinfunction "EQ9_P$12") (pintype "bidirectional"))
      (node (ref "VSENSE8") (pin "1") (pinfunction "1_1") (pintype "passive"))
    )
    (net (code "25") (name "/EQ10") (class "Default")
      (node (ref "2KΩ9") (pin "P$1") (pinfunction "P$1_P$1") (pintype "bidirectional"))
      (node (ref "U$49") (pin "P$10") (pinfunction "EQ10_P$10") (pintype "bidirectional"))
      (node (ref "VSENSE9") (pin "1") (pinfunction "1_1") (pintype "passive"))
    )
    (net (code "26") (name "/EQ11") (class "Default")
      (node (ref "2KΩ10") (pin "P$1") (pinfunction "P$1_P$1") (pintype "bidirectional"))
      (node (ref "U$49") (pin "P$8") (pinfunction "EQ11_P$8") (pintype "bidirectional"))
      (node (ref "VSENSE10") (pin "1") (pinfunction "1_1") (pintype "passive"))
    )
    (net (code "27") (name "/EQ12") (class "Default")
      (node (ref "2KΩ11") (pin "P$1") (pinfunction "P$1_P$1") (pintype "bidirectional"))
      (node (ref "U$49") (pin "P$6") (pinfunction "EQ12_P$6") (pintype "bidirectional"))
      (node (ref "VSENSE11") (pin "1") (pinfunction "1_1") (pintype "passive"))
    )
    (net (code "28") (name "/EQ13") (class "Default")
      (node (ref "2KΩ12") (pin "P$1") (pinfunction "P$1_P$1") (pintype "bidirectional"))
      (node (ref "U$49") (pin "P$4") (pinfunction "EQ13_P$4") (pintype "bidirectional"))
      (node (ref "VSENSE12") (pin "1") (pinfunction "1_1") (pintype "passive"))
    )
    (net (code "29") (name "/EQ14") (class "Default")
      (node (ref "2KΩ13") (pin "P$1") (pinfunction "P$1_P$1") (pintype "bidirectional"))
      (node (ref "U$49") (pin "P$2") (pinfunction "EQ14_P$2") (pintype "bidirectional"))
      (node (ref "VSENSE13") (pin "1") (pinfunction "1_1") (pintype "passive"))
    )
    (net (code "30") (name "/EQ15") (class "Default")
      (node (ref "2KΩ14") (pin "P$1") (pinfunction "P$1_P$1") (pintype "bidirectional"))
      (node (ref "U$49") (pin "P$80") (pinfunction "EQ15_P$80") (pintype "bidirectional"))
      (node (ref "VSENSE14") (pin "1") (pinfunction "1_1") (pintype "passive"))
    )
    (net (code "31") (name "/EQ16") (class "Default")
      (node (ref "2KΩ15") (pin "P$1") (pinfunction "P$1_P$1") (pintype "bidirectional"))
      (node (ref "U$49") (pin "P$78") (pinfunction "EQ16_P$78") (pintype "bidirectional"))
      (node (ref "VSENSE15") (pin "1") (pinfunction "1_1") (pintype "passive"))
    )
    (net (code "32") (name "/FAULTH+") (class "Default")
      (node (ref "U$49") (pin "P$57") (pinfunction "FAULTH+_P$57") (pintype "bidirectional"))
    )
    (net (code "33") (name "/FAULTH-") (class "Default")
      (node (ref "U$49") (pin "P$56") (pinfunction "FAULTH-_P$56") (pintype "bidirectional"))
    )
    (net (code "34") (name "/FAULTL+") (class "Default")
      (node (ref "U$49") (pin "P$50") (pinfunction "FAULTL+_P$50") (pintype "bidirectional"))
    )
    (net (code "35") (name "/FAULTL-") (class "Default")
      (node (ref "U$49") (pin "P$51") (pinfunction "FAULTL-_P$51") (pintype "bidirectional"))
    )
    (net (code "36") (name "/OUT1") (class "Default")
      (node (ref "U$49") (pin "P$68") (pinfunction "OUT2_P$68") (pintype "bidirectional"))
      (node (ref "U$49") (pin "P$73") (pinfunction "OUT1_P$73") (pintype "bidirectional"))
      (node (ref "U$59") (pin "P$2") (pinfunction "P$2_P$2") (pintype "bidirectional"))
    )
    (net (code "37") (name "/TOP") (class "Default")
      (node (ref "U$49") (pin "P$76") (pinfunction "TOP_P$76") (pintype "bidirectional"))
      (node (ref "U$63") (pin "P$2") (pinfunction "P$2_P$2") (pintype "bidirectional"))
    )
    (net (code "38") (name "/UART-INPUT") (class "Default")
      (node (ref "U$49") (pin "P$39") (pinfunction "RX_P$39") (pintype "bidirectional"))
    )
    (net (code "39") (name "/UART-OUTPUT") (class "Default")
      (node (ref "U$49") (pin "P$38") (pinfunction "TX_P$38") (pintype "bidirectional"))
    )
    (net (code "40") (name "/VDIG") (class "Default")
      (node (ref "U$49") (pin "P$34") (pinfunction "VDIG_P$34") (pintype "bidirectional"))
      (node (ref "U$49") (pin "P$41") (pinfunction "VIO_P$41") (pintype "bidirectional"))
      (node (ref "U$53") (pin "P$1") (pinfunction "P$1_P$1") (pintype "bidirectional"))
      (node (ref "U$54") (pin "P$1") (pinfunction "P$1_P$1") (pintype "bidirectional"))
      (node (ref "U$55") (pin "P$1") (pinfunction "P$1_P$1") (pintype "bidirectional"))
    )
    (net (code "41") (name "/VP") (class "Default")
      (node (ref "U$53") (pin "P$2") (pinfunction "P$2_P$2") (pintype "bidirectional"))
    )
    (net (code "42") (name "/VSENSE0") (class "Default")
      (node (ref "100Ω") (pin "P$1") (pinfunction "P$1_P$1") (pintype "bidirectional"))
      (node (ref "U$49") (pin "P$29") (pinfunction "VSENSE0_P$29") (pintype "bidirectional"))
      (node (ref "U$5") (pin "P$2") (pinfunction "P$2_P$2") (pintype "bidirectional"))
      (node (ref "VSENSE0") (pin "2") (pinfunction "2_2") (pintype "passive"))
    )
    (net (code "43") (name "/VSENSE1") (class "Default")
      (node (ref "100Ω1") (pin "P$1") (pinfunction "P$1_P$1") (pintype "bidirectional"))
      (node (ref "1UF") (pin "P$1") (pinfunction "P$1_P$1") (pintype "bidirectional"))
      (node (ref "U$2") (pin "P$2") (pinfunction "P$2_P$2") (pintype "bidirectional"))
      (node (ref "U$49") (pin "P$27") (pinfunction "VSENSE1_P$27") (pintype "bidirectional"))
      (node (ref "U$5") (pin "P$1") (pinfunction "P$1_P$1") (pintype "bidirectional"))
      (node (ref "U$8") (pin "P$2") (pinfunction "P$2_P$2") (pintype "bidirectional"))
      (node (ref "VSENSE1") (pin "2") (pinfunction "2_2") (pintype "passive"))
    )
    (net (code "44") (name "/VSENSE2") (class "Default")
      (node (ref "100Ω2") (pin "P$1") (pinfunction "P$1_P$1") (pintype "bidirectional"))
      (node (ref "1UF1") (pin "P$1") (pinfunction "P$1_P$1") (pintype "bidirectional"))
      (node (ref "U$2") (pin "P$1") (pinfunction "P$1_P$1") (pintype "bidirectional"))
      (node (ref "U$3") (pin "P$2") (pinfunction "P$2_P$2") (pintype "bidirectional"))
      (node (ref "U$49") (pin "P$25") (pinfunction "VSENSE2_P$25") (pintype "bidirectional"))
      (node (ref "U$7") (pin "P$2") (pinfunction "P$2_P$2") (pintype "bidirectional"))
      (node (ref "VSENSE2") (pin "2") (pinfunction "2_2") (pintype "passive"))
    )
    (net (code "45") (name "/VSENSE3") (class "Default")
      (node (ref "100Ω3") (pin "P$1") (pinfunction "P$1_P$1") (pintype "bidirectional"))
      (node (ref "1UF2") (pin "P$1") (pinfunction "P$1_P$1") (pintype "bidirectional"))
      (node (ref "U$11") (pin "P$2") (pinfunction "P$2_P$2") (pintype "bidirectional"))
      (node (ref "U$49") (pin "P$23") (pinfunction "VSENSE3_P$23") (pintype "bidirectional"))
      (node (ref "U$7") (pin "P$1") (pinfunction "P$1_P$1") (pintype "bidirectional"))
      (node (ref "U$9") (pin "P$2") (pinfunction "P$2_P$2") (pintype "bidirectional"))
      (node (ref "VSENSE3") (pin "2") (pinfunction "2_2") (pintype "passive"))
    )
    (net (code "46") (name "/VSENSE4") (class "Default")
      (node (ref "100Ω4") (pin "P$1") (pinfunction "P$1_P$1") (pintype "bidirectional"))
      (node (ref "1UF3") (pin "P$1") (pinfunction "P$1_P$1") (pintype "bidirectional"))
      (node (ref "U$11") (pin "P$1") (pinfunction "P$1_P$1") (pintype "bidirectional"))
      (node (ref "U$12") (pin "P$2") (pinfunction "P$2_P$2") (pintype "bidirectional"))
      (node (ref "U$14") (pin "P$2") (pinfunction "P$2_P$2") (pintype "bidirectional"))
      (node (ref "U$49") (pin "P$21") (pinfunction "VSENSE4_P$21") (pintype "bidirectional"))
      (node (ref "VSENSE4") (pin "2") (pinfunction "2_2") (pintype "passive"))
    )
    (net (code "47") (name "/VSENSE5") (class "Default")
      (node (ref "100Ω5") (pin "P$1") (pinfunction "P$1_P$1") (pintype "bidirectional"))
      (node (ref "1UF4") (pin "P$1") (pinfunction "P$1_P$1") (pintype "bidirectional"))
      (node (ref "U$14") (pin "P$1") (pinfunction "P$1_P$1") (pintype "bidirectional"))
      (node (ref "U$15") (pin "P$2") (pinfunction "P$2_P$2") (pintype "bidirectional"))
      (node (ref "U$17") (pin "P$2") (pinfunction "P$2_P$2") (pintype "bidirectional"))
      (node (ref "U$49") (pin "P$19") (pinfunction "VSENSE5_P$19") (pintype "bidirectional"))
      (node (ref "VSENSE5") (pin "2") (pinfunction "2_2") (pintype "passive"))
    )
    (net (code "48") (name "/VSENSE6") (class "Default")
      (node (ref "100Ω6") (pin "P$1") (pinfunction "P$1_P$1") (pintype "bidirectional"))
      (node (ref "1UF5") (pin "P$1") (pinfunction "P$1_P$1") (pintype "bidirectional"))
      (node (ref "U$17") (pin "P$1") (pinfunction "P$1_P$1") (pintype "bidirectional"))
      (node (ref "U$18") (pin "P$2") (pinfunction "P$2_P$2") (pintype "bidirectional"))
      (node (ref "U$20") (pin "P$2") (pinfunction "P$2_P$2") (pintype "bidirectional"))
      (node (ref "U$49") (pin "P$17") (pinfunction "VSENSE6_P$17") (pintype "bidirectional"))
      (node (ref "VSENSE6") (pin "2") (pinfunction "2_2") (pintype "passive"))
    )
    (net (code "49") (name "/VSENSE7") (class "Default")
      (node (ref "100Ω7") (pin "P$1") (pinfunction "P$1_P$1") (pintype "bidirectional"))
      (node (ref "1UF6") (pin "P$1") (pinfunction "P$1_P$1") (pintype "bidirectional"))
      (node (ref "U$20") (pin "P$1") (pinfunction "P$1_P$1") (pintype "bidirectional"))
      (node (ref "U$21") (pin "P$2") (pinfunction "P$2_P$2") (pintype "bidirectional"))
      (node (ref "U$23") (pin "P$2") (pinfunction "P$2_P$2") (pintype "bidirectional"))
      (node (ref "U$49") (pin "P$15") (pinfunction "VSENSE7_P$15") (pintype "bidirectional"))
      (node (ref "VSENSE7") (pin "2") (pinfunction "2_2") (pintype "passive"))
    )
    (net (code "50") (name "/VSENSE8") (class "Default")
      (node (ref "100Ω8") (pin "P$1") (pinfunction "P$1_P$1") (pintype "bidirectional"))
      (node (ref "1UF7") (pin "P$1") (pinfunction "P$1_P$1") (pintype "bidirectional"))
      (node (ref "U$23") (pin "P$1") (pinfunction "P$1_P$1") (pintype "bidirectional"))
      (node (ref "U$24") (pin "P$2") (pinfunction "P$2_P$2") (pintype "bidirectional"))
      (node (ref "U$26") (pin "P$2") (pinfunction "P$2_P$2") (pintype "bidirectional"))
      (node (ref "U$49") (pin "P$13") (pinfunction "VSENSE8_P$13") (pintype "bidirectional"))
      (node (ref "VSENSE8") (pin "2") (pinfunction "2_2") (pintype "passive"))
    )
    (net (code "51") (name "/VSENSE9") (class "Default")
      (node (ref "100Ω9") (pin "P$1") (pinfunction "P$1_P$1") (pintype "bidirectional"))
      (node (ref "1UF8") (pin "P$1") (pinfunction "P$1_P$1") (pintype "bidirectional"))
      (node (ref "U$26") (pin "P$1") (pinfunction "P$1_P$1") (pintype "bidirectional"))
      (node (ref "U$27") (pin "P$2") (pinfunction "P$2_P$2") (pintype "bidirectional"))
      (node (ref "U$29") (pin "P$2") (pinfunction "P$2_P$2") (pintype "bidirectional"))
      (node (ref "U$49") (pin "P$11") (pinfunction "VSENSE9_P$11") (pintype "bidirectional"))
      (node (ref "VSENSE9") (pin "2") (pinfunction "2_2") (pintype "passive"))
    )
    (net (code "52") (name "/VSENSE10") (class "Default")
      (node (ref "100Ω10") (pin "P$1") (pinfunction "P$1_P$1") (pintype "bidirectional"))
      (node (ref "1UF9") (pin "P$1") (pinfunction "P$1_P$1") (pintype "bidirectional"))
      (node (ref "U$29") (pin "P$1") (pinfunction "P$1_P$1") (pintype "bidirectional"))
      (node (ref "U$30") (pin "P$2") (pinfunction "P$2_P$2") (pintype "bidirectional"))
      (node (ref "U$32") (pin "P$2") (pinfunction "P$2_P$2") (pintype "bidirectional"))
      (node (ref "U$49") (pin "P$9") (pinfunction "VSENSE10_P$9") (pintype "bidirectional"))
      (node (ref "VSENSE10") (pin "2") (pinfunction "2_2") (pintype "passive"))
    )
    (net (code "53") (name "/VSENSE11") (class "Default")
      (node (ref "100Ω11") (pin "P$1") (pinfunction "P$1_P$1") (pintype "bidirectional"))
      (node (ref "1UF10") (pin "P$1") (pinfunction "P$1_P$1") (pintype "bidirectional"))
      (node (ref "U$32") (pin "P$1") (pinfunction "P$1_P$1") (pintype "bidirectional"))
      (node (ref "U$33") (pin "P$2") (pinfunction "P$2_P$2") (pintype "bidirectional"))
      (node (ref "U$35") (pin "P$2") (pinfunction "P$2_P$2") (pintype "bidirectional"))
      (node (ref "U$49") (pin "P$7") (pinfunction "VSENSE11_P$7") (pintype "bidirectional"))
      (node (ref "VSENSE11") (pin "2") (pinfunction "2_2") (pintype "passive"))
    )
    (net (code "54") (name "/VSENSE12") (class "Default")
      (node (ref "100Ω12") (pin "P$1") (pinfunction "P$1_P$1") (pintype "bidirectional"))
      (node (ref "1UF11") (pin "P$1") (pinfunction "P$1_P$1") (pintype "bidirectional"))
      (node (ref "U$35") (pin "P$1") (pinfunction "P$1_P$1") (pintype "bidirectional"))
      (node (ref "U$36") (pin "P$2") (pinfunction "P$2_P$2") (pintype "bidirectional"))
      (node (ref "U$38") (pin "P$2") (pinfunction "P$2_P$2") (pintype "bidirectional"))
      (node (ref "U$49") (pin "P$5") (pinfunction "VSENSE12_P$5") (pintype "bidirectional"))
      (node (ref "VSENSE12") (pin "2") (pinfunction "2_2") (pintype "passive"))
    )
    (net (code "55") (name "/VSENSE13") (class "Default")
      (node (ref "100Ω13") (pin "P$1") (pinfunction "P$1_P$1") (pintype "bidirectional"))
      (node (ref "1UF12") (pin "P$1") (pinfunction "P$1_P$1") (pintype "bidirectional"))
      (node (ref "U$38") (pin "P$1") (pinfunction "P$1_P$1") (pintype "bidirectional"))
      (node (ref "U$39") (pin "P$2") (pinfunction "P$2_P$2") (pintype "bidirectional"))
      (node (ref "U$41") (pin "P$2") (pinfunction "P$2_P$2") (pintype "bidirectional"))
      (node (ref "U$49") (pin "P$3") (pinfunction "VSENSE13_P$3") (pintype "bidirectional"))
      (node (ref "VSENSE13") (pin "2") (pinfunction "2_2") (pintype "passive"))
    )
    (net (code "56") (name "/VSENSE14") (class "Default")
      (node (ref "100Ω14") (pin "P$1") (pinfunction "P$1_P$1") (pintype "bidirectional"))
      (node (ref "1UF13") (pin "P$1") (pinfunction "P$1_P$1") (pintype "bidirectional"))
      (node (ref "U$41") (pin "P$1") (pinfunction "P$1_P$1") (pintype "bidirectional"))
      (node (ref "U$42") (pin "P$2") (pinfunction "P$2_P$2") (pintype "bidirectional"))
      (node (ref "U$44") (pin "P$2") (pinfunction "P$2_P$2") (pintype "bidirectional"))
      (node (ref "U$49") (pin "P$1") (pinfunction "VSENSE14_P$1") (pintype "bidirectional"))
      (node (ref "VSENSE14") (pin "2") (pinfunction "2_2") (pintype "passive"))
    )
    (net (code "57") (name "/VSENSE15") (class "Default")
      (node (ref "100Ω15") (pin "P$1") (pinfunction "P$1_P$1") (pintype "bidirectional"))
      (node (ref "1UF14") (pin "P$1") (pinfunction "P$1_P$1") (pintype "bidirectional"))
      (node (ref "U$44") (pin "P$1") (pinfunction "P$1_P$1") (pintype "bidirectional"))
      (node (ref "U$45") (pin "P$2") (pinfunction "P$2_P$2") (pintype "bidirectional"))
      (node (ref "U$47") (pin "P$2") (pinfunction "P$2_P$2") (pintype "bidirectional"))
      (node (ref "U$49") (pin "P$79") (pinfunction "VSENSE15_P$79") (pintype "bidirectional"))
      (node (ref "VSENSE15") (pin "2") (pinfunction "2_2") (pintype "passive"))
    )
    (net (code "58") (name "/VSENSE16") (class "Default")
      (node (ref "1UF15") (pin "P$1") (pinfunction "P$1_P$1") (pintype "bidirectional"))
      (node (ref "J1") (pin "1") (pinfunction "1_1") (pintype "passive"))
      (node (ref "U$47") (pin "P$1") (pinfunction "P$1_P$1") (pintype "bidirectional"))
      (node (ref "U$48") (pin "P$2") (pinfunction "P$2_P$2") (pintype "bidirectional"))
      (node (ref "U$49") (pin "P$77") (pinfunction "VSENSE16_P$77") (pintype "bidirectional"))
    )
    (net (code "59") (name "GND") (class "Default")
      (node (ref "+") (pin "1") (pinfunction "1_1") (pintype "passive"))
      (node (ref "100KΩ") (pin "P$2") (pinfunction "P$2_P$2") (pintype "bidirectional"))
      (node (ref "100Ω") (pin "P$2") (pinfunction "P$2_P$2") (pintype "bidirectional"))
      (node (ref "1UF") (pin "P$2") (pinfunction "P$2_P$2") (pintype "bidirectional"))
      (node (ref "1UF1") (pin "P$2") (pinfunction "P$2_P$2") (pintype "bidirectional"))
      (node (ref "1UF10") (pin "P$2") (pinfunction "P$2_P$2") (pintype "bidirectional"))
      (node (ref "1UF11") (pin "P$2") (pinfunction "P$2_P$2") (pintype "bidirectional"))
      (node (ref "1UF12") (pin "P$2") (pinfunction "P$2_P$2") (pintype "bidirectional"))
      (node (ref "1UF13") (pin "P$2") (pinfunction "P$2_P$2") (pintype "bidirectional"))
      (node (ref "1UF14") (pin "P$2") (pinfunction "P$2_P$2") (pintype "bidirectional"))
      (node (ref "1UF15") (pin "P$2") (pinfunction "P$2_P$2") (pintype "bidirectional"))
      (node (ref "1UF2") (pin "P$2") (pinfunction "P$2_P$2") (pintype "bidirectional"))
      (node (ref "1UF3") (pin "P$2") (pinfunction "P$2_P$2") (pintype "bidirectional"))
      (node (ref "1UF4") (pin "P$2") (pinfunction "P$2_P$2") (pintype "bidirectional"))
      (node (ref "1UF5") (pin "P$2") (pinfunction "P$2_P$2") (pintype "bidirectional"))
      (node (ref "1UF6") (pin "P$2") (pinfunction "P$2_P$2") (pintype "bidirectional"))
      (node (ref "1UF7") (pin "P$2") (pinfunction "P$2_P$2") (pintype "bidirectional"))
      (node (ref "1UF8") (pin "P$2") (pinfunction "P$2_P$2") (pintype "bidirectional"))
      (node (ref "1UF9") (pin "P$2") (pinfunction "P$2_P$2") (pintype "bidirectional"))
      (node (ref "U$4") (pin "P$3") (pinfunction "SOURCE_P$3") (pintype "bidirectional"))
      (node (ref "U$49") (pin "P$30") (pinfunction "DGND1_P$30") (pintype "bidirectional"))
      (node (ref "U$49") (pin "P$35") (pinfunction "DG_ND2_P$35") (pintype "bidirectional"))
      (node (ref "U$49") (pin "P$37") (pinfunction "DG_ND3_P$37") (pintype "bidirectional"))
      (node (ref "U$49") (pin "P$48") (pinfunction "CGND_P$48") (pintype "bidirectional"))
      (node (ref "U$49") (pin "P$49") (pinfunction "WAKEUP_P$49") (pintype "bidirectional"))
      (node (ref "U$49") (pin "P$69") (pinfunction "AGND3_P$69") (pintype "bidirectional"))
      (node (ref "U$49") (pin "P$72") (pinfunction "AGND2_P$72") (pintype "bidirectional"))
      (node (ref "U$49") (pin "P$74") (pinfunction "AGND1_P$74") (pintype "bidirectional"))
      (node (ref "U$51") (pin "P$2") (pinfunction "P$2_P$2") (pintype "bidirectional"))
      (node (ref "U$52") (pin "P$2") (pinfunction "P$2_P$2") (pintype "bidirectional"))
      (node (ref "U$54") (pin "P$2") (pinfunction "P$2_P$2") (pintype "bidirectional"))
      (node (ref "U$55") (pin "P$2") (pinfunction "P$2_P$2") (pintype "bidirectional"))
      (node (ref "U$56") (pin "P$2") (pinfunction "P$2_P$2") (pintype "bidirectional"))
      (node (ref "U$57") (pin "P$1") (pinfunction "P$1_P$1") (pintype "bidirectional"))
      (node (ref "U$58") (pin "P$1") (pinfunction "P$1_P$1") (pintype "bidirectional"))
      (node (ref "U$59") (pin "P$1") (pinfunction "P$1_P$1") (pintype "bidirectional"))
      (node (ref "U$60") (pin "P$1") (pinfunction "P$1_P$1") (pintype "bidirectional"))
      (node (ref "U$62") (pin "P$2") (pinfunction "P$2_P$2") (pintype "bidirectional"))
    )
    (net (code "60") (name "Net-(+12-Pad2)") (class "Default")
      (node (ref "+12") (pin "2") (pinfunction "2_2") (pintype "passive"))
      (node (ref "75Ω12") (pin "P$1") (pinfunction "P$1_P$1") (pintype "bidirectional"))
      (node (ref "U$39") (pin "P$1") (pinfunction "P$1_P$1") (pintype "bidirectional"))
    )
    (net (code "61") (name "Net-(+13-Pad2)") (class "Default")
      (node (ref "+13") (pin "2") (pinfunction "2_2") (pintype "passive"))
      (node (ref "75Ω13") (pin "P$1") (pinfunction "P$1_P$1") (pintype "bidirectional"))
      (node (ref "U$42") (pin "P$1") (pinfunction "P$1_P$1") (pintype "bidirectional"))
    )
    (net (code "62") (name "Net-(+14-Pad2)") (class "Default")
      (node (ref "+14") (pin "2") (pinfunction "2_2") (pintype "passive"))
      (node (ref "75Ω14") (pin "P$1") (pinfunction "P$1_P$1") (pintype "bidirectional"))
      (node (ref "U$45") (pin "P$1") (pinfunction "P$1_P$1") (pintype "bidirectional"))
    )
    (net (code "63") (name "Net-(+15-Pad2)") (class "Default")
      (node (ref "+15") (pin "2") (pinfunction "2_2") (pintype "passive"))
      (node (ref "75Ω15") (pin "P$1") (pinfunction "P$1_P$1") (pintype "bidirectional"))
      (node (ref "TOPCELL") (pin "1") (pinfunction "1_1") (pintype "passive"))
      (node (ref "U$48") (pin "P$1") (pinfunction "P$1_P$1") (pintype "bidirectional"))
      (node (ref "U$63") (pin "P$1") (pinfunction "P$1_P$1") (pintype "bidirectional"))
    )
    (net (code "64") (name "Net-(U$1-DRAIN)") (class "Default")
      (node (ref "75Ω1") (pin "P$2") (pinfunction "P$2_P$2") (pintype "bidirectional"))
      (node (ref "U$1") (pin "P$2") (pinfunction "DRAIN_P$2") (pintype "bidirectional"))
    )
    (net (code "65") (name "Net-(U$1-GATE)") (class "Default")
      (node (ref "100KΩ1") (pin "P$1") (pinfunction "P$1_P$1") (pintype "bidirectional"))
      (node (ref "2KΩ1") (pin "P$2") (pinfunction "P$2_P$2") (pintype "bidirectional"))
      (node (ref "U$1") (pin "P$1") (pinfunction "GATE_P$1") (pintype "bidirectional"))
    )
    (net (code "66") (name "Net-(U$1-SOURCE)") (class "Default")
      (node (ref "+") (pin "2") (pinfunction "2_2") (pintype "passive"))
      (node (ref "+1") (pin "1") (pinfunction "1_1") (pintype "passive"))
      (node (ref "100KΩ1") (pin "P$2") (pinfunction "P$2_P$2") (pintype "bidirectional"))
      (node (ref "100Ω1") (pin "P$2") (pinfunction "P$2_P$2") (pintype "bidirectional"))
      (node (ref "75Ω") (pin "P$1") (pinfunction "P$1_P$1") (pintype "bidirectional"))
      (node (ref "U$1") (pin "P$3") (pinfunction "SOURCE_P$3") (pintype "bidirectional"))
      (node (ref "U$8") (pin "P$1") (pinfunction "P$1_P$1") (pintype "bidirectional"))
    )
    (net (code "67") (name "Net-(U$4-DRAIN)") (class "Default")
      (node (ref "75Ω") (pin "P$2") (pinfunction "P$2_P$2") (pintype "bidirectional"))
      (node (ref "U$4") (pin "P$2") (pinfunction "DRAIN_P$2") (pintype "bidirectional"))
    )
    (net (code "68") (name "Net-(U$4-GATE)") (class "Default")
      (node (ref "100KΩ") (pin "P$1") (pinfunction "P$1_P$1") (pintype "bidirectional"))
      (node (ref "2KΩ") (pin "P$2") (pinfunction "P$2_P$2") (pintype "bidirectional"))
      (node (ref "U$4") (pin "P$1") (pinfunction "GATE_P$1") (pintype "bidirectional"))
    )
    (net (code "69") (name "Net-(U$6-DRAIN)") (class "Default")
      (node (ref "75Ω2") (pin "P$2") (pinfunction "P$2_P$2") (pintype "bidirectional"))
      (node (ref "U$6") (pin "P$2") (pinfunction "DRAIN_P$2") (pintype "bidirectional"))
    )
    (net (code "70") (name "Net-(U$6-GATE)") (class "Default")
      (node (ref "100KΩ2") (pin "P$1") (pinfunction "P$1_P$1") (pintype "bidirectional"))
      (node (ref "2KΩ2") (pin "P$2") (pinfunction "P$2_P$2") (pintype "bidirectional"))
      (node (ref "U$6") (pin "P$1") (pinfunction "GATE_P$1") (pintype "bidirectional"))
    )
    (net (code "71") (name "Net-(U$6-SOURCE)") (class "Default")
      (node (ref "+1") (pin "2") (pinfunction "2_2") (pintype "passive"))
      (node (ref "+2") (pin "1") (pinfunction "1_1") (pintype "passive"))
      (node (ref "100KΩ2") (pin "P$2") (pinfunction "P$2_P$2") (pintype "bidirectional"))
      (node (ref "100Ω2") (pin "P$2") (pinfunction "P$2_P$2") (pintype "bidirectional"))
      (node (ref "75Ω1") (pin "P$1") (pinfunction "P$1_P$1") (pintype "bidirectional"))
      (node (ref "U$3") (pin "P$1") (pinfunction "P$1_P$1") (pintype "bidirectional"))
      (node (ref "U$6") (pin "P$3") (pinfunction "SOURCE_P$3") (pintype "bidirectional"))
    )
    (net (code "72") (name "Net-(U$10-DRAIN)") (class "Default")
      (node (ref "75Ω3") (pin "P$2") (pinfunction "P$2_P$2") (pintype "bidirectional"))
      (node (ref "U$10") (pin "P$2") (pinfunction "DRAIN_P$2") (pintype "bidirectional"))
    )
    (net (code "73") (name "Net-(U$10-GATE)") (class "Default")
      (node (ref "100KΩ3") (pin "P$1") (pinfunction "P$1_P$1") (pintype "bidirectional"))
      (node (ref "2KΩ3") (pin "P$2") (pinfunction "P$2_P$2") (pintype "bidirectional"))
      (node (ref "U$10") (pin "P$1") (pinfunction "GATE_P$1") (pintype "bidirectional"))
    )
    (net (code "74") (name "Net-(U$10-SOURCE)") (class "Default")
      (node (ref "+2") (pin "2") (pinfunction "2_2") (pintype "passive"))
      (node (ref "+3") (pin "1") (pinfunction "1_1") (pintype "passive"))
      (node (ref "100KΩ3") (pin "P$2") (pinfunction "P$2_P$2") (pintype "bidirectional"))
      (node (ref "100Ω3") (pin "P$2") (pinfunction "P$2_P$2") (pintype "bidirectional"))
      (node (ref "75Ω2") (pin "P$1") (pinfunction "P$1_P$1") (pintype "bidirectional"))
      (node (ref "U$10") (pin "P$3") (pinfunction "SOURCE_P$3") (pintype "bidirectional"))
      (node (ref "U$9") (pin "P$1") (pinfunction "P$1_P$1") (pintype "bidirectional"))
    )
    (net (code "75") (name "Net-(U$13-DRAIN)") (class "Default")
      (node (ref "75Ω4") (pin "P$2") (pinfunction "P$2_P$2") (pintype "bidirectional"))
      (node (ref "U$13") (pin "P$2") (pinfunction "DRAIN_P$2") (pintype "bidirectional"))
    )
    (net (code "76") (name "Net-(U$13-GATE)") (class "Default")
      (node (ref "100KΩ4") (pin "P$1") (pinfunction "P$1_P$1") (pintype "bidirectional"))
      (node (ref "2KΩ4") (pin "P$2") (pinfunction "P$2_P$2") (pintype "bidirectional"))
      (node (ref "U$13") (pin "P$1") (pinfunction "GATE_P$1") (pintype "bidirectional"))
    )
    (net (code "77") (name "Net-(U$16-DRAIN)") (class "Default")
      (node (ref "75Ω5") (pin "P$2") (pinfunction "P$2_P$2") (pintype "bidirectional"))
      (node (ref "U$16") (pin "P$2") (pinfunction "DRAIN_P$2") (pintype "bidirectional"))
    )
    (net (code "78") (name "Net-(U$16-GATE)") (class "Default")
      (node (ref "100KΩ5") (pin "P$1") (pinfunction "P$1_P$1") (pintype "bidirectional"))
      (node (ref "2KΩ5") (pin "P$2") (pinfunction "P$2_P$2") (pintype "bidirectional"))
      (node (ref "U$16") (pin "P$1") (pinfunction "GATE_P$1") (pintype "bidirectional"))
    )
    (net (code "79") (name "Net-(U$16-SOURCE)") (class "Default")
      (node (ref "+4") (pin "2") (pinfunction "2_2") (pintype "passive"))
      (node (ref "+5") (pin "1") (pinfunction "1_1") (pintype "passive"))
      (node (ref "100KΩ5") (pin "P$2") (pinfunction "P$2_P$2") (pintype "bidirectional"))
      (node (ref "100Ω5") (pin "P$2") (pinfunction "P$2_P$2") (pintype "bidirectional"))
      (node (ref "75Ω4") (pin "P$1") (pinfunction "P$1_P$1") (pintype "bidirectional"))
      (node (ref "U$15") (pin "P$1") (pinfunction "P$1_P$1") (pintype "bidirectional"))
      (node (ref "U$16") (pin "P$3") (pinfunction "SOURCE_P$3") (pintype "bidirectional"))
    )
    (net (code "80") (name "Net-(U$19-DRAIN)") (class "Default")
      (node (ref "75Ω6") (pin "P$2") (pinfunction "P$2_P$2") (pintype "bidirectional"))
      (node (ref "U$19") (pin "P$2") (pinfunction "DRAIN_P$2") (pintype "bidirectional"))
    )
    (net (code "81") (name "Net-(U$19-GATE)") (class "Default")
      (node (ref "100KΩ6") (pin "P$1") (pinfunction "P$1_P$1") (pintype "bidirectional"))
      (node (ref "2KΩ6") (pin "P$2") (pinfunction "P$2_P$2") (pintype "bidirectional"))
      (node (ref "U$19") (pin "P$1") (pinfunction "GATE_P$1") (pintype "bidirectional"))
    )
    (net (code "82") (name "Net-(U$19-SOURCE)") (class "Default")
      (node (ref "+5") (pin "2") (pinfunction "2_2") (pintype "passive"))
      (node (ref "+6") (pin "1") (pinfunction "1_1") (pintype "passive"))
      (node (ref "100KΩ6") (pin "P$2") (pinfunction "P$2_P$2") (pintype "bidirectional"))
      (node (ref "100Ω6") (pin "P$2") (pinfunction "P$2_P$2") (pintype "bidirectional"))
      (node (ref "75Ω5") (pin "P$1") (pinfunction "P$1_P$1") (pintype "bidirectional"))
      (node (ref "U$18") (pin "P$1") (pinfunction "P$1_P$1") (pintype "bidirectional"))
      (node (ref "U$19") (pin "P$3") (pinfunction "SOURCE_P$3") (pintype "bidirectional"))
    )
    (net (code "83") (name "Net-(U$22-DRAIN)") (class "Default")
      (node (ref "75Ω7") (pin "P$2") (pinfunction "P$2_P$2") (pintype "bidirectional"))
      (node (ref "U$22") (pin "P$2") (pinfunction "DRAIN_P$2") (pintype "bidirectional"))
    )
    (net (code "84") (name "Net-(U$22-GATE)") (class "Default")
      (node (ref "100KΩ7") (pin "P$1") (pinfunction "P$1_P$1") (pintype "bidirectional"))
      (node (ref "2KΩ7") (pin "P$2") (pinfunction "P$2_P$2") (pintype "bidirectional"))
      (node (ref "U$22") (pin "P$1") (pinfunction "GATE_P$1") (pintype "bidirectional"))
    )
    (net (code "85") (name "Net-(U$22-SOURCE)") (class "Default")
      (node (ref "+6") (pin "2") (pinfunction "2_2") (pintype "passive"))
      (node (ref "+7") (pin "1") (pinfunction "1_1") (pintype "passive"))
      (node (ref "100KΩ7") (pin "P$2") (pinfunction "P$2_P$2") (pintype "bidirectional"))
      (node (ref "100Ω7") (pin "P$2") (pinfunction "P$2_P$2") (pintype "bidirectional"))
      (node (ref "75Ω6") (pin "P$1") (pinfunction "P$1_P$1") (pintype "bidirectional"))
      (node (ref "U$21") (pin "P$1") (pinfunction "P$1_P$1") (pintype "bidirectional"))
      (node (ref "U$22") (pin "P$3") (pinfunction "SOURCE_P$3") (pintype "bidirectional"))
    )
    (net (code "86") (name "Net-(U$25-DRAIN)") (class "Default")
      (node (ref "75Ω8") (pin "P$2") (pinfunction "P$2_P$2") (pintype "bidirectional"))
      (node (ref "U$25") (pin "P$2") (pinfunction "DRAIN_P$2") (pintype "bidirectional"))
    )
    (net (code "87") (name "Net-(U$25-GATE)") (class "Default")
      (node (ref "100KΩ8") (pin "P$1") (pinfunction "P$1_P$1") (pintype "bidirectional"))
      (node (ref "2KΩ8") (pin "P$2") (pinfunction "P$2_P$2") (pintype "bidirectional"))
      (node (ref "U$25") (pin "P$1") (pinfunction "GATE_P$1") (pintype "bidirectional"))
    )
    (net (code "88") (name "Net-(U$28-DRAIN)") (class "Default")
      (node (ref "75Ω9") (pin "P$2") (pinfunction "P$2_P$2") (pintype "bidirectional"))
      (node (ref "U$28") (pin "P$2") (pinfunction "DRAIN_P$2") (pintype "bidirectional"))
    )
    (net (code "89") (name "Net-(U$28-GATE)") (class "Default")
      (node (ref "100KΩ9") (pin "P$1") (pinfunction "P$1_P$1") (pintype "bidirectional"))
      (node (ref "2KΩ9") (pin "P$2") (pinfunction "P$2_P$2") (pintype "bidirectional"))
      (node (ref "U$28") (pin "P$1") (pinfunction "GATE_P$1") (pintype "bidirectional"))
    )
    (net (code "90") (name "Net-(U$28-SOURCE)") (class "Default")
      (node (ref "+8") (pin "2") (pinfunction "2_2") (pintype "passive"))
      (node (ref "+9") (pin "1") (pinfunction "1_1") (pintype "passive"))
      (node (ref "100KΩ9") (pin "P$2") (pinfunction "P$2_P$2") (pintype "bidirectional"))
      (node (ref "100Ω9") (pin "P$2") (pinfunction "P$2_P$2") (pintype "bidirectional"))
      (node (ref "75Ω8") (pin "P$1") (pinfunction "P$1_P$1") (pintype "bidirectional"))
      (node (ref "U$27") (pin "P$1") (pinfunction "P$1_P$1") (pintype "bidirectional"))
      (node (ref "U$28") (pin "P$3") (pinfunction "SOURCE_P$3") (pintype "bidirectional"))
    )
    (net (code "91") (name "Net-(U$31-DRAIN)") (class "Default")
      (node (ref "75Ω10") (pin "P$2") (pinfunction "P$2_P$2") (pintype "bidirectional"))
      (node (ref "U$31") (pin "P$2") (pinfunction "DRAIN_P$2") (pintype "bidirectional"))
    )
    (net (code "92") (name "Net-(U$31-GATE)") (class "Default")
      (node (ref "100KΩ10") (pin "P$1") (pinfunction "P$1_P$1") (pintype "bidirectional"))
      (node (ref "2KΩ10") (pin "P$2") (pinfunction "P$2_P$2") (pintype "bidirectional"))
      (node (ref "U$31") (pin "P$1") (pinfunction "GATE_P$1") (pintype "bidirectional"))
    )
    (net (code "93") (name "Net-(U$31-SOURCE)") (class "Default")
      (node (ref "+10") (pin "1") (pinfunction "1_1") (pintype "passive"))
      (node (ref "+9") (pin "2") (pinfunction "2_2") (pintype "passive"))
      (node (ref "100KΩ10") (pin "P$2") (pinfunction "P$2_P$2") (pintype "bidirectional"))
      (node (ref "100Ω10") (pin "P$2") (pinfunction "P$2_P$2") (pintype "bidirectional"))
      (node (ref "75Ω9") (pin "P$1") (pinfunction "P$1_P$1") (pintype "bidirectional"))
      (node (ref "U$30") (pin "P$1") (pinfunction "P$1_P$1") (pintype "bidirectional"))
      (node (ref "U$31") (pin "P$3") (pinfunction "SOURCE_P$3") (pintype "bidirectional"))
    )
    (net (code "94") (name "Net-(U$34-DRAIN)") (class "Default")
      (node (ref "75Ω11") (pin "P$2") (pinfunction "P$2_P$2") (pintype "bidirectional"))
      (node (ref "U$34") (pin "P$2") (pinfunction "DRAIN_P$2") (pintype "bidirectional"))
    )
    (net (code "95") (name "Net-(U$34-GATE)") (class "Default")
      (node (ref "100KΩ11") (pin "P$1") (pinfunction "P$1_P$1") (pintype "bidirectional"))
      (node (ref "2KΩ11") (pin "P$2") (pinfunction "P$2_P$2") (pintype "bidirectional"))
      (node (ref "U$34") (pin "P$1") (pinfunction "GATE_P$1") (pintype "bidirectional"))
    )
    (net (code "96") (name "Net-(U$34-SOURCE)") (class "Default")
      (node (ref "+10") (pin "2") (pinfunction "2_2") (pintype "passive"))
      (node (ref "+11") (pin "1") (pinfunction "1_1") (pintype "passive"))
      (node (ref "100KΩ11") (pin "P$2") (pinfunction "P$2_P$2") (pintype "bidirectional"))
      (node (ref "100Ω11") (pin "P$2") (pinfunction "P$2_P$2") (pintype "bidirectional"))
      (node (ref "75Ω10") (pin "P$1") (pinfunction "P$1_P$1") (pintype "bidirectional"))
      (node (ref "U$33") (pin "P$1") (pinfunction "P$1_P$1") (pintype "bidirectional"))
      (node (ref "U$34") (pin "P$3") (pinfunction "SOURCE_P$3") (pintype "bidirectional"))
    )
    (net (code "97") (name "Net-(U$37-DRAIN)") (class "Default")
      (node (ref "75Ω12") (pin "P$2") (pinfunction "P$2_P$2") (pintype "bidirectional"))
      (node (ref "U$37") (pin "P$2") (pinfunction "DRAIN_P$2") (pintype "bidirectional"))
    )
    (net (code "98") (name "Net-(U$37-GATE)") (class "Default")
      (node (ref "100KΩ12") (pin "P$1") (pinfunction "P$1_P$1") (pintype "bidirectional"))
      (node (ref "2KΩ12") (pin "P$2") (pinfunction "P$2_P$2") (pintype "bidirectional"))
      (node (ref "U$37") (pin "P$1") (pinfunction "GATE_P$1") (pintype "bidirectional"))
    )
    (net (code "99") (name "Net-(U$40-DRAIN)") (class "Default")
      (node (ref "75Ω13") (pin "P$2") (pinfunction "P$2_P$2") (pintype "bidirectional"))
      (node (ref "U$40") (pin "P$2") (pinfunction "DRAIN_P$2") (pintype "bidirectional"))
    )
    (net (code "100") (name "Net-(U$40-GATE)") (class "Default")
      (node (ref "100KΩ13") (pin "P$1") (pinfunction "P$1_P$1") (pintype "bidirectional"))
      (node (ref "2KΩ13") (pin "P$2") (pinfunction "P$2_P$2") (pintype "bidirectional"))
      (node (ref "U$40") (pin "P$1") (pinfunction "GATE_P$1") (pintype "bidirectional"))
    )
    (net (code "101") (name "Net-(U$40-SOURCE)") (class "Default")
      (node (ref "+13") (pin "1") (pinfunction "1_1") (pintype "passive"))
      (node (ref "100KΩ13") (pin "P$2") (pinfunction "P$2_P$2") (pintype "bidirectional"))
      (node (ref "100Ω13") (pin "P$2") (pinfunction "P$2_P$2") (pintype "bidirectional"))
      (node (ref "U$40") (pin "P$3") (pinfunction "SOURCE_P$3") (pintype "bidirectional"))
    )
    (net (code "102") (name "Net-(U$43-DRAIN)") (class "Default")
      (node (ref "75Ω14") (pin "P$2") (pinfunction "P$2_P$2") (pintype "bidirectional"))
      (node (ref "U$43") (pin "P$2") (pinfunction "DRAIN_P$2") (pintype "bidirectional"))
    )
    (net (code "103") (name "Net-(U$43-GATE)") (class "Default")
      (node (ref "100KΩ14") (pin "P$1") (pinfunction "P$1_P$1") (pintype "bidirectional"))
      (node (ref "2KΩ14") (pin "P$2") (pinfunction "P$2_P$2") (pintype "bidirectional"))
      (node (ref "U$43") (pin "P$1") (pinfunction "GATE_P$1") (pintype "bidirectional"))
    )
    (net (code "104") (name "Net-(U$43-SOURCE)") (class "Default")
      (node (ref "+14") (pin "1") (pinfunction "1_1") (pintype "passive"))
      (node (ref "100KΩ14") (pin "P$2") (pinfunction "P$2_P$2") (pintype "bidirectional"))
      (node (ref "100Ω14") (pin "P$2") (pinfunction "P$2_P$2") (pintype "bidirectional"))
      (node (ref "U$43") (pin "P$3") (pinfunction "SOURCE_P$3") (pintype "bidirectional"))
    )
    (net (code "105") (name "Net-(U$46-DRAIN)") (class "Default")
      (node (ref "75Ω15") (pin "P$2") (pinfunction "P$2_P$2") (pintype "bidirectional"))
      (node (ref "U$46") (pin "P$2") (pinfunction "DRAIN_P$2") (pintype "bidirectional"))
    )
    (net (code "106") (name "Net-(U$46-GATE)") (class "Default")
      (node (ref "100KΩ15") (pin "P$1") (pinfunction "P$1_P$1") (pintype "bidirectional"))
      (node (ref "2KΩ15") (pin "P$2") (pinfunction "P$2_P$2") (pintype "bidirectional"))
      (node (ref "U$46") (pin "P$1") (pinfunction "GATE_P$1") (pintype "bidirectional"))
    )
    (net (code "107") (name "Net-(U$46-SOURCE)") (class "Default")
      (node (ref "+15") (pin "1") (pinfunction "1_1") (pintype "passive"))
      (node (ref "100KΩ15") (pin "P$2") (pinfunction "P$2_P$2") (pintype "bidirectional"))
      (node (ref "100Ω15") (pin "P$2") (pinfunction "P$2_P$2") (pintype "bidirectional"))
      (node (ref "U$46") (pin "P$3") (pinfunction "SOURCE_P$3") (pintype "bidirectional"))
    )
    (net (code "108") (name "Net-(U$49-CHM)") (class "Default")
      (node (ref "U$49") (pin "P$33") (pinfunction "CHM_P$33") (pintype "bidirectional"))
      (node (ref "U$50") (pin "P$2") (pinfunction "P$2_P$2") (pintype "bidirectional"))
    )
    (net (code "109") (name "Net-(U$49-CHP)") (class "Default")
      (node (ref "U$49") (pin "P$32") (pinfunction "CHP_P$32") (pintype "bidirectional"))
      (node (ref "U$50") (pin "P$1") (pinfunction "P$1_P$1") (pintype "bidirectional"))
    )
    (net (code "110") (name "Net-(U$49-GPIO0)") (class "Default")
      (node (ref "GPIO_0-6") (pin "1") (pinfunction "1_1") (pintype "passive"))
      (node (ref "U$49") (pin "P$47") (pinfunction "GPIO0_P$47") (pintype "bidirectional"))
    )
    (net (code "111") (name "Net-(U$49-GPIO1)") (class "Default")
      (node (ref "GPIO_0-6") (pin "2") (pinfunction "2_2") (pintype "passive"))
      (node (ref "U$49") (pin "P$46") (pinfunction "GPIO1_P$46") (pintype "bidirectional"))
    )
    (net (code "112") (name "Net-(U$49-GPIO2)") (class "Default")
      (node (ref "GPIO_0-6") (pin "3") (pinfunction "3_3") (pintype "passive"))
      (node (ref "U$49") (pin "P$45") (pinfunction "GPIO2_P$45") (pintype "bidirectional"))
    )
    (net (code "113") (name "Net-(U$49-GPIO3)") (class "Default")
      (node (ref "GPIO_0-6") (pin "4") (pinfunction "4_4") (pintype "passive"))
      (node (ref "U$49") (pin "P$44") (pinfunction "GPIO3_P$44") (pintype "bidirectional"))
    )
    (net (code "114") (name "Net-(U$49-GPIO4)") (class "Default")
      (node (ref "GPIO_0-6") (pin "5") (pinfunction "5_5") (pintype "passive"))
      (node (ref "U$49") (pin "P$43") (pinfunction "GPIO4_P$43") (pintype "bidirectional"))
    )
    (net (code "115") (name "Net-(U$49-GPIO5)") (class "Default")
      (node (ref "GPIO_0-6") (pin "6") (pinfunction "6_6") (pintype "passive"))
      (node (ref "U$49") (pin "P$42") (pinfunction "GPIO5_P$42") (pintype "bidirectional"))
    )
    (net (code "116") (name "Net-(U$49-V5VAO)") (class "Default")
      (node (ref "U$49") (pin "P$58") (pinfunction "V5VAO_P$58") (pintype "bidirectional"))
      (node (ref "U$56") (pin "P$1") (pinfunction "P$1_P$1") (pintype "bidirectional"))
    )
    (net (code "117") (name "Net-(U$49-VM)") (class "Default")
      (node (ref "U$49") (pin "P$31") (pinfunction "VM_P$31") (pintype "bidirectional"))
      (node (ref "U$51") (pin "P$1") (pinfunction "P$1_P$1") (pintype "bidirectional"))
      (node (ref "U$52") (pin "P$1") (pinfunction "P$1_P$1") (pintype "bidirectional"))
    )
    (net (code "118") (name "Net-(U$49-VP)") (class "Default")
      (node (ref "U$49") (pin "P$70") (pinfunction "VP_P$70") (pintype "bidirectional"))
      (node (ref "U$60") (pin "P$2") (pinfunction "P$2_P$2") (pintype "bidirectional"))
      (node (ref "U$61") (pin "P$2") (pinfunction "P$2_P$2") (pintype "bidirectional"))
    )
    (net (code "119") (name "Net-(U$49-VREF)") (class "Default")
      (node (ref "U$49") (pin "P$67") (pinfunction "VREF_P$67") (pintype "bidirectional"))
      (node (ref "U$57") (pin "P$2") (pinfunction "P$2_P$2") (pintype "bidirectional"))
      (node (ref "U$58") (pin "P$2") (pinfunction "P$2_P$2") (pintype "bidirectional"))
    )
    (net (code "120") (name "Net-(U$61-PadP$1)") (class "Default")
      (node (ref "U$61") (pin "P$1") (pinfunction "P$1_P$1") (pintype "bidirectional"))
      (node (ref "U$62") (pin "P$1") (pinfunction "P$1_P$1") (pintype "bidirectional"))
    )
    (net (code "121") (name "unconnected-(U$49-FAULT_N-PadP$40)") (class "Default")
      (node (ref "U$49") (pin "P$40") (pinfunction "FAULT_N_P$40") (pintype "bidirectional"))
    )
    (net (code "122") (name "unconnected-(U$49-NC1-PadP$36)") (class "Default")
      (node (ref "U$49") (pin "P$36") (pinfunction "NC1_P$36") (pintype "bidirectional"))
    )
    (net (code "123") (name "unconnected-(U$49-NC2-PadP$75)") (class "Default")
      (node (ref "U$49") (pin "P$75") (pinfunction "NC2_P$75") (pintype "bidirectional"))
    )
    (net (code "124") (name "unconnected-(U$49-NPNB-PadP$71)") (class "Default")
      (node (ref "U$49") (pin "P$71") (pinfunction "NPNB_P$71") (pintype "bidirectional"))
    )
  )
)
